# CoCoFlash_v1_04c.net
KiCad netlist of a schematic drawn in EAGLE
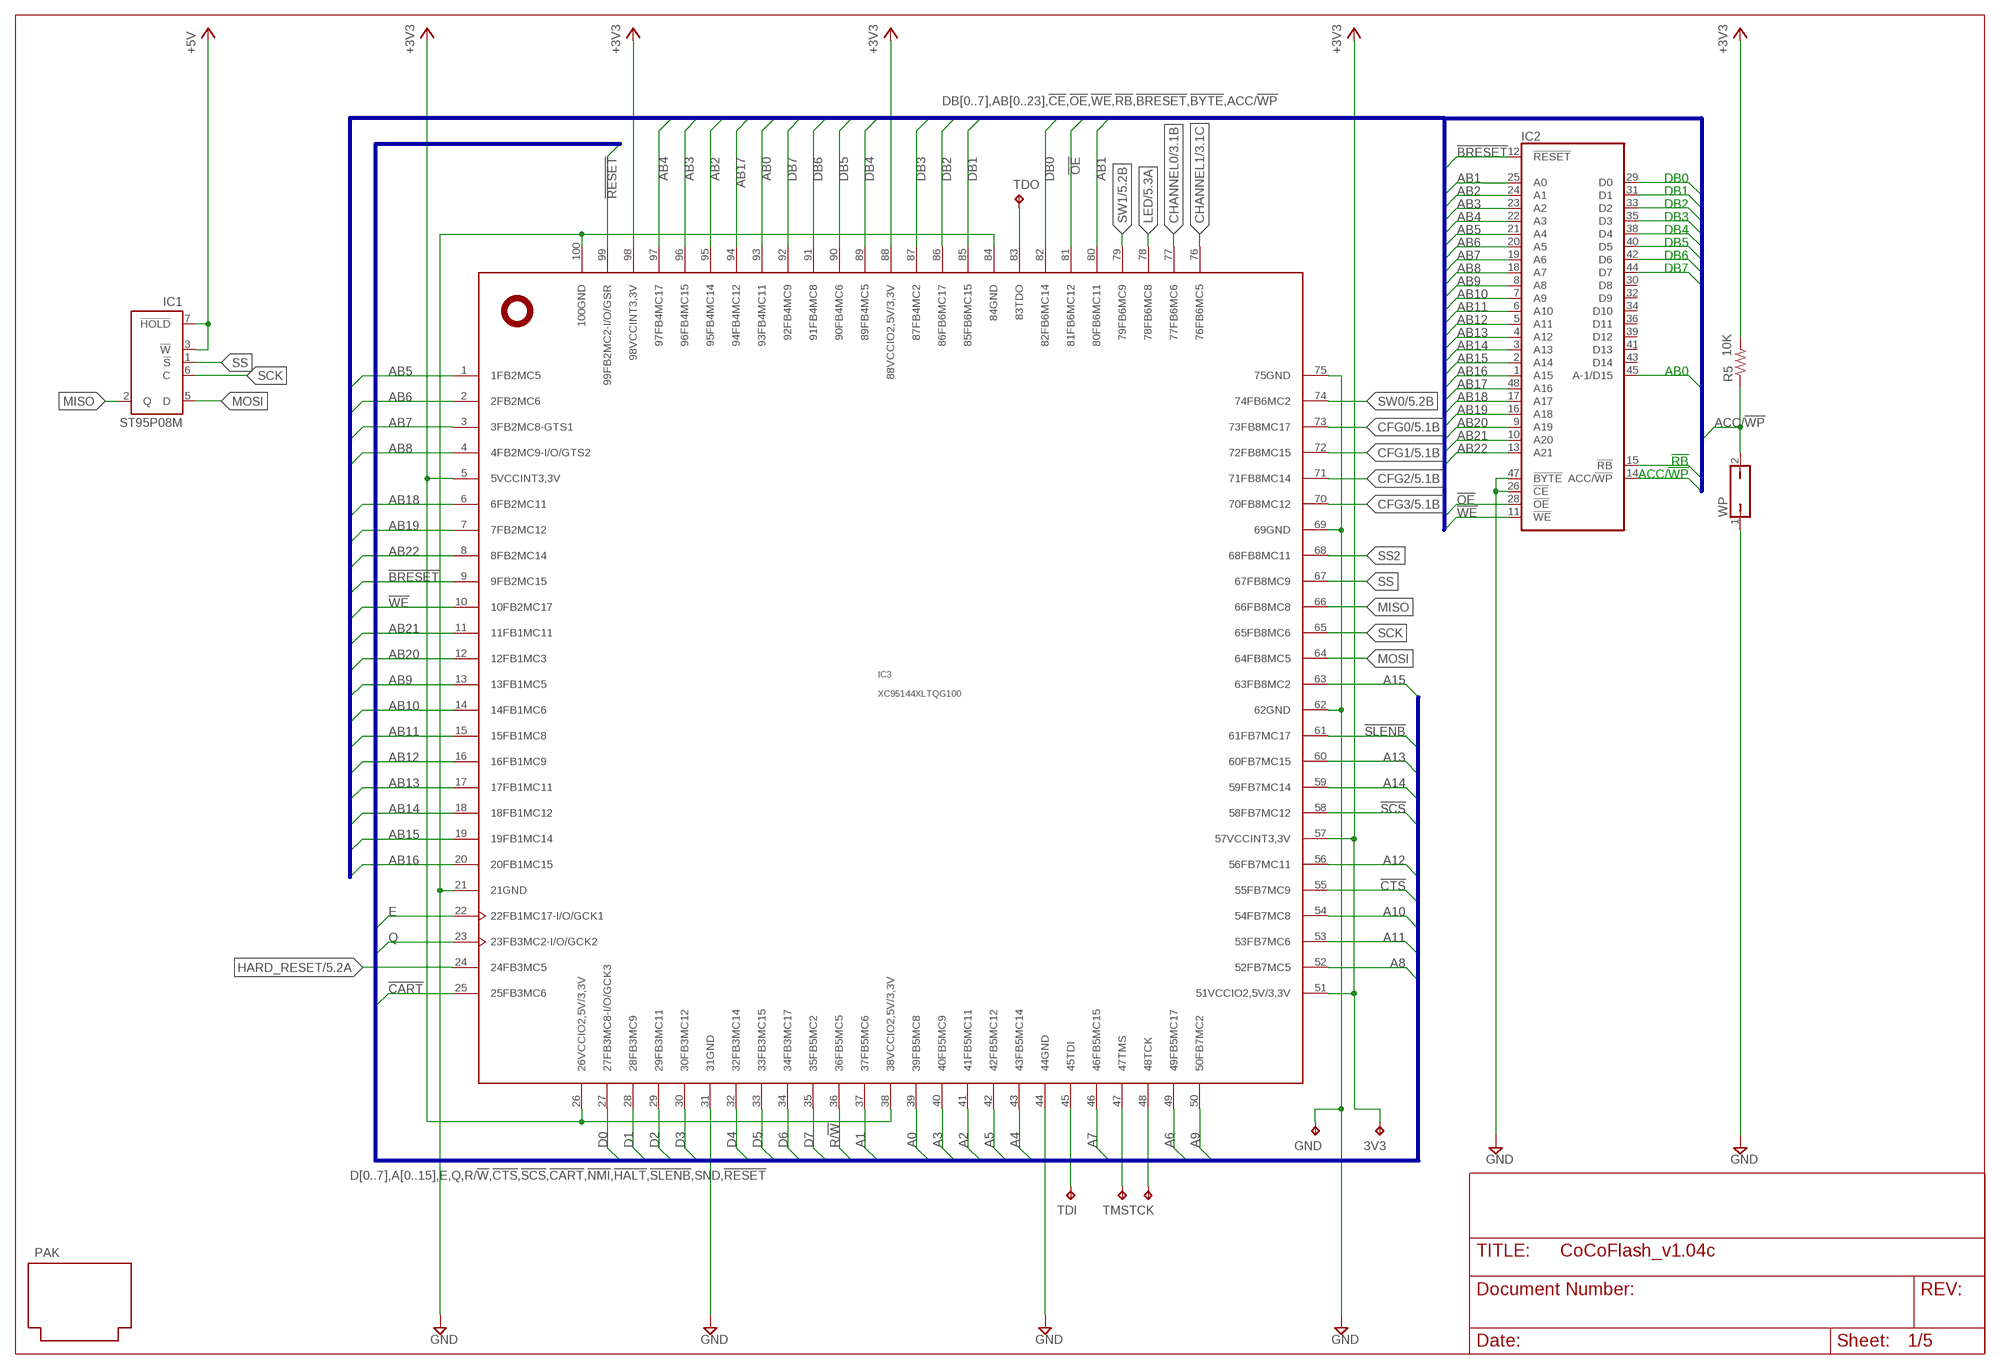
[diagram p0: schematic, sheet 1]
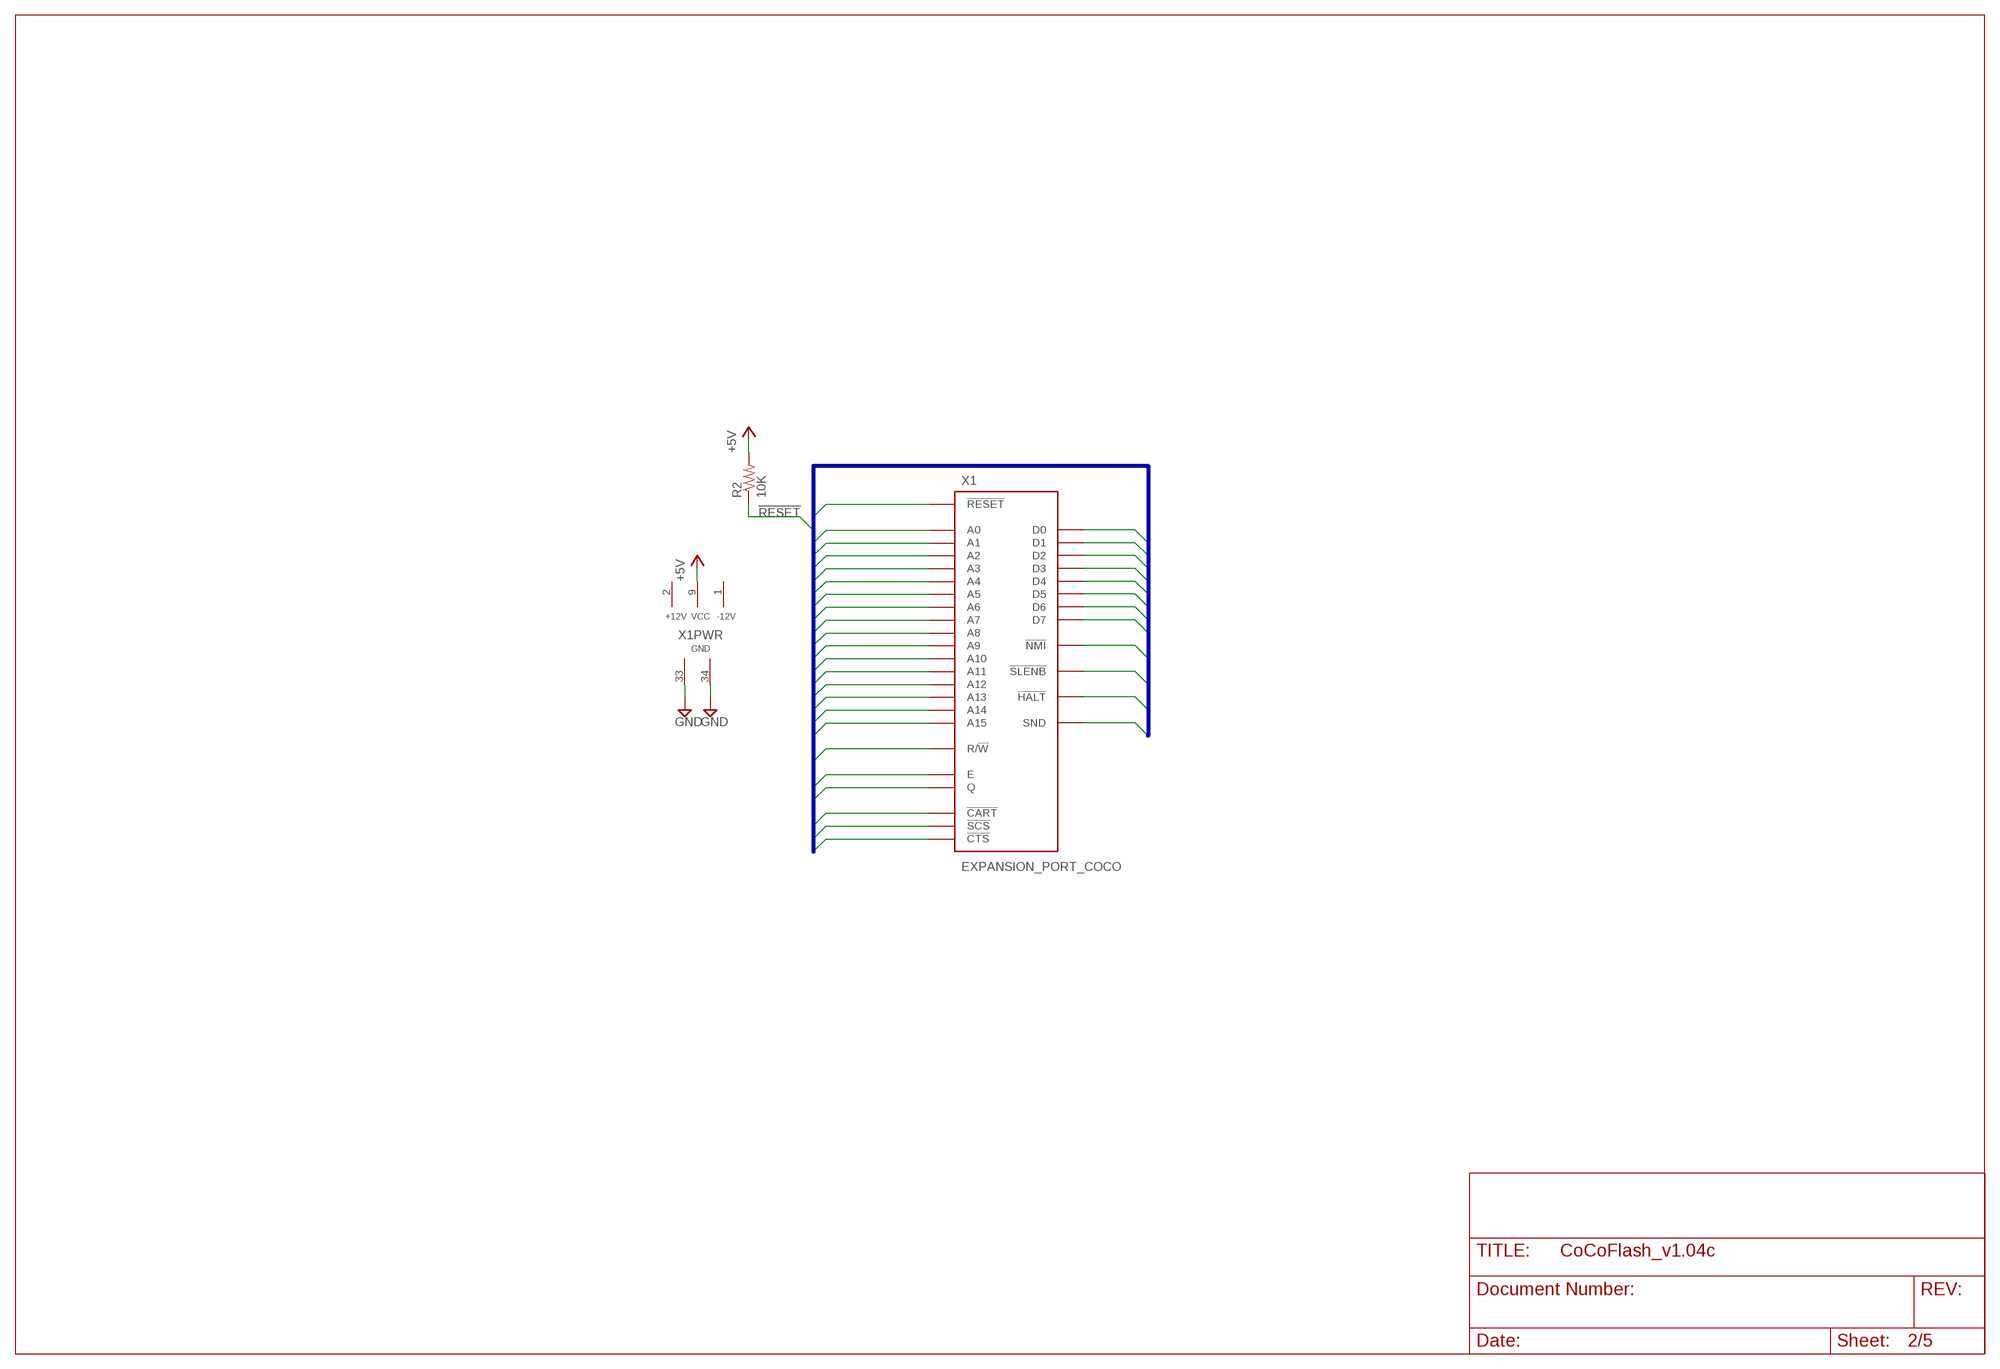
[diagram p1: schematic, sheet 2]
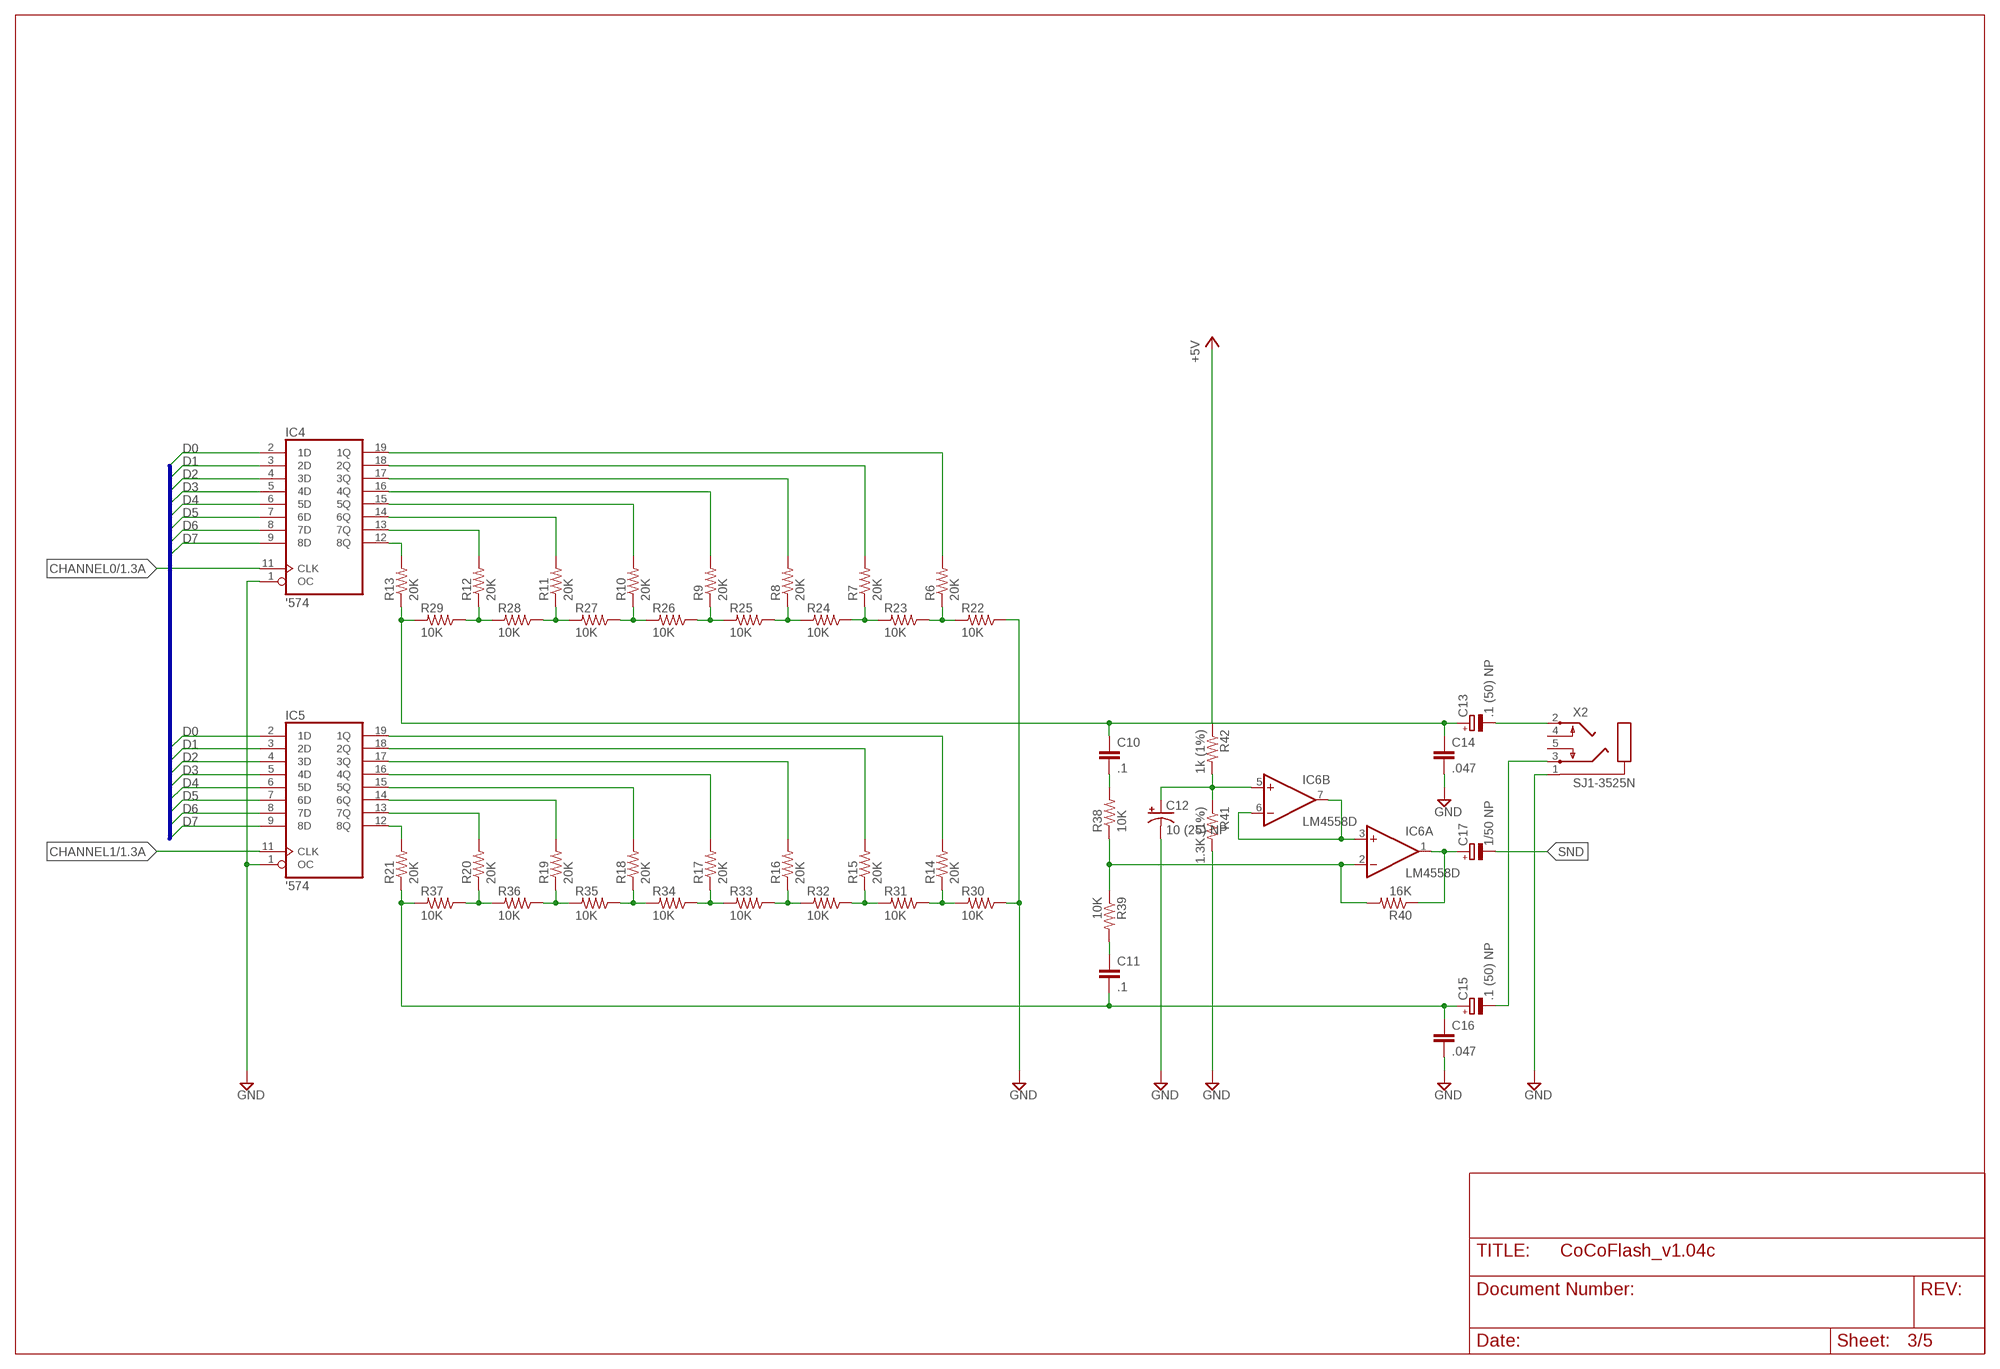
[diagram p2: schematic, sheet 3]
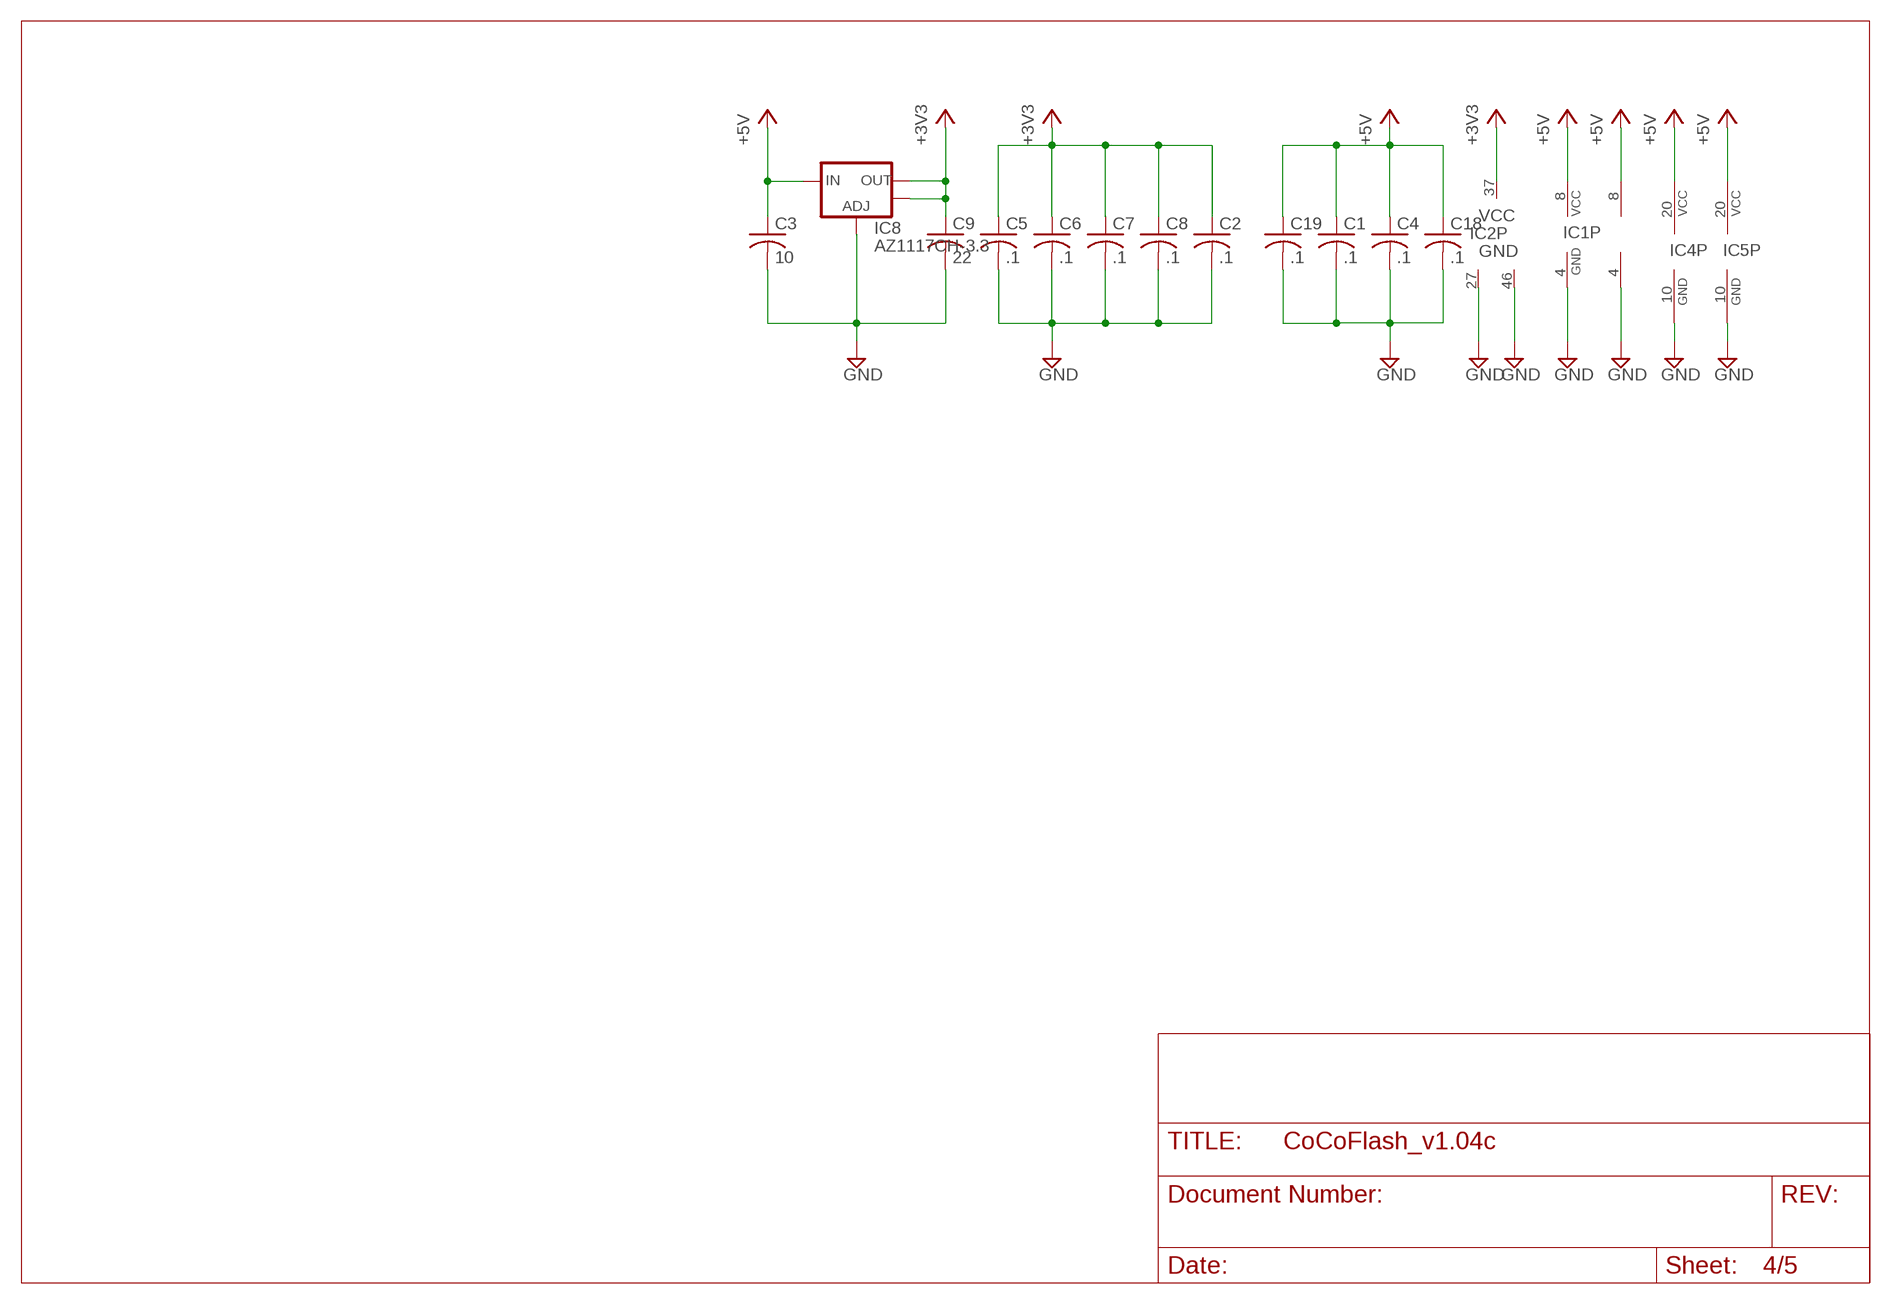
[diagram p3: schematic, sheet 4]
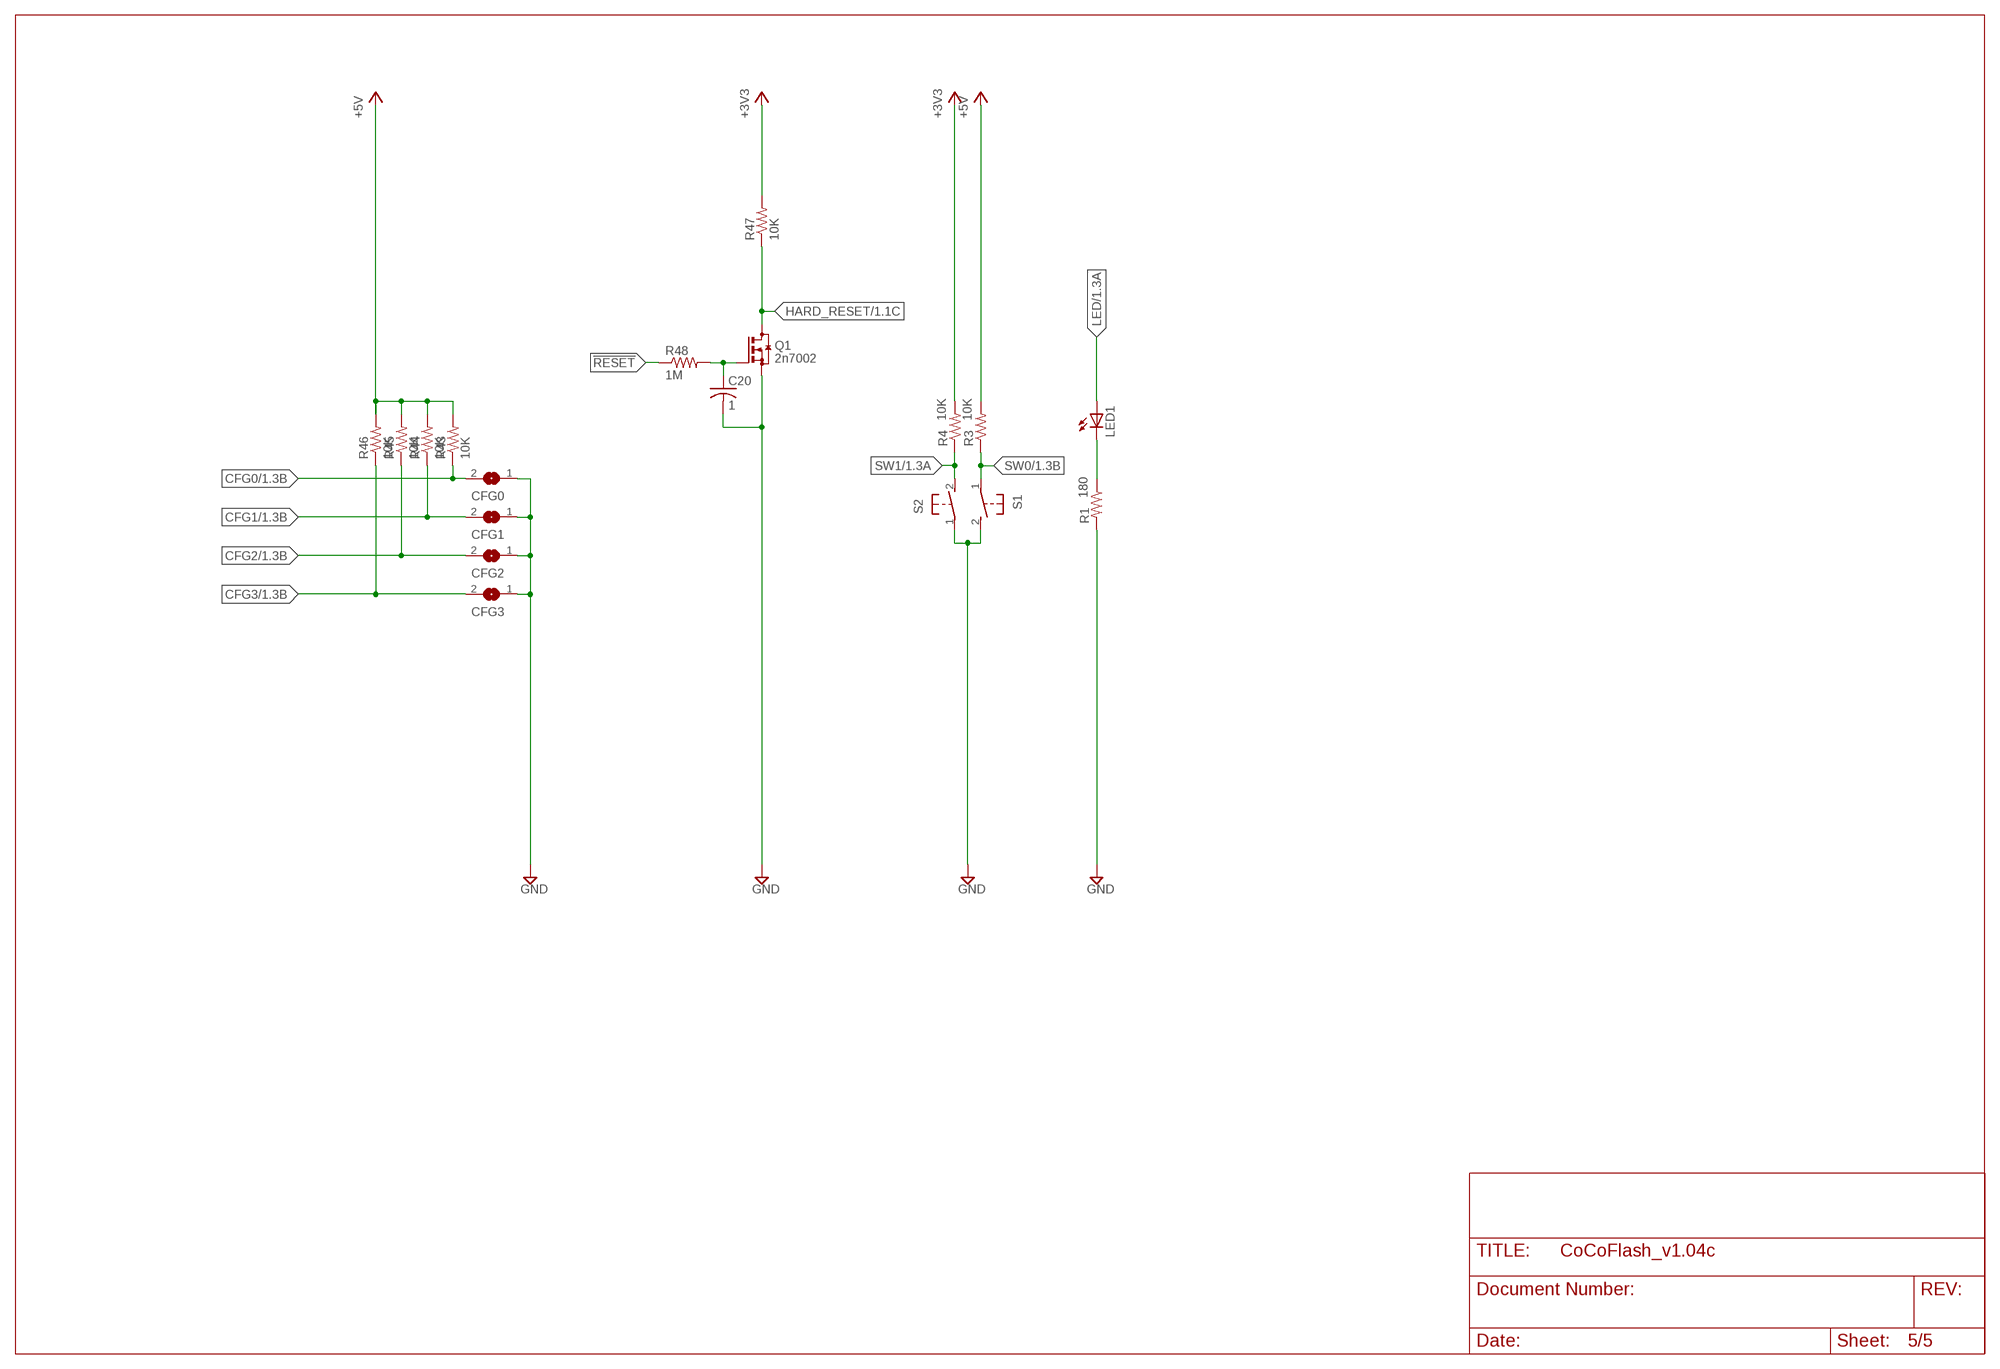
[diagram p4: schematic, sheet 5]

(export (version "E")
  (design (tool "Eeschema 10.0.6"))
  (components
    (comp (ref "R2")
      (value "10K")
      (footprint "eagle-import:R0402")
      (libsource (lib "eagle-import") (part "resistor_R-US_R0402"))
    )
    (comp (ref "X1")
      (value "EXPANSION_PORT_COCO")
      (footprint "eagle-import:MA20-2")
      (libsource (lib "eagle-import") (part "EXPANSION_PORT_COCO"))
    )
    (comp (ref "3V3")
      (value "TPTP08R")
      (footprint "eagle-import:TP08R")
      (libsource (lib "eagle-import") (part "TPTP08R"))
    )
    (comp (ref "GND")
      (value "TPTP08R")
      (footprint "eagle-import:TP08R")
      (libsource (lib "eagle-import") (part "TPTP08R"))
    )
    (comp (ref "IC1")
      (value "ST95P08M")
      (footprint "eagle-import:SO08")
      (libsource (lib "eagle-import") (part "ST95P08M"))
    )
    (comp (ref "IC2")
      (value "MX29LV640")
      (footprint "eagle-import:TSOP48")
      (libsource (lib "eagle-import") (part "MX29LV640"))
    )
    (comp (ref "IC3")
      (value "XC95144XLTQG100")
      (footprint "eagle-import:TQFP100")
      (libsource (lib "eagle-import") (part "XC95144XLTQG100"))
    )
    (comp (ref "PAK")
      (value "PROGRAM_PAK")
      (footprint "eagle-import:PROGRAM_PAK")
      (libsource (lib "eagle-import") (part "PROGRAM_PAK"))
    )
    (comp (ref "R5")
      (value "10K")
      (footprint "eagle-import:R0402")
      (libsource (lib "eagle-import") (part "R-US_R0402"))
    )
    (comp (ref "TCK")
      (value "TPTP08R")
      (footprint "eagle-import:TP08R")
      (libsource (lib "eagle-import") (part "TPTP08R"))
    )
    (comp (ref "TDI")
      (value "TPTP08R")
      (footprint "eagle-import:TP08R")
      (libsource (lib "eagle-import") (part "TPTP08R"))
    )
    (comp (ref "TDO")
      (value "TPTP08R")
      (footprint "eagle-import:TP08R")
      (libsource (lib "eagle-import") (part "TPTP08R"))
    )
    (comp (ref "TMS")
      (value "TPTP08R")
      (footprint "eagle-import:TP08R")
      (libsource (lib "eagle-import") (part "TPTP08R"))
    )
    (comp (ref "WP")
      (value "JP1Q")
      (footprint "eagle-import:JP1")
      (libsource (lib "eagle-import") (part "JP1Q"))
    )
    (comp (ref "C20")
      (value "1")
      (footprint "eagle-import:C0402")
      (libsource (lib "eagle-import") (part "C-USC0402"))
    )
    (comp (ref "CFG0")
      (value "SJ")
      (footprint "eagle-import:SJ")
      (libsource (lib "eagle-import") (part "SJ"))
    )
    (comp (ref "CFG1")
      (value "SJ")
      (footprint "eagle-import:SJ")
      (libsource (lib "eagle-import") (part "SJ"))
    )
    (comp (ref "CFG2")
      (value "SJ")
      (footprint "eagle-import:SJ")
      (libsource (lib "eagle-import") (part "SJ"))
    )
    (comp (ref "CFG3")
      (value "SJ")
      (footprint "eagle-import:SJ")
      (libsource (lib "eagle-import") (part "SJ"))
    )
    (comp (ref "LED1")
      (value "LED3MM")
      (footprint "eagle-import:LED3MM")
      (libsource (lib "eagle-import") (part "LED3MM"))
    )
    (comp (ref "Q1")
      (value "2n7002")
      (footprint "eagle-import:SOT23")
      (libsource (lib "eagle-import") (part "BSS123"))
    )
    (comp (ref "R1")
      (value "180")
      (footprint "eagle-import:R0402")
      (libsource (lib "eagle-import") (part "R-US_R0402"))
    )
    (comp (ref "R3")
      (value "10K")
      (footprint "eagle-import:R0402")
      (libsource (lib "eagle-import") (part "R-US_R0402"))
    )
    (comp (ref "R4")
      (value "10K")
      (footprint "eagle-import:R0402")
      (libsource (lib "eagle-import") (part "R-US_R0402"))
    )
    (comp (ref "R43")
      (value "10K")
      (footprint "eagle-import:R0402")
      (libsource (lib "eagle-import") (part "R-US_R0402"))
    )
    (comp (ref "R44")
      (value "10K")
      (footprint "eagle-import:R0402")
      (libsource (lib "eagle-import") (part "R-US_R0402"))
    )
    (comp (ref "R45")
      (value "10K")
      (footprint "eagle-import:R0402")
      (libsource (lib "eagle-import") (part "R-US_R0402"))
    )
    (comp (ref "R46")
      (value "10K")
      (footprint "eagle-import:R0402")
      (libsource (lib "eagle-import") (part "R-US_R0402"))
    )
    (comp (ref "R47")
      (value "10K")
      (footprint "eagle-import:R0402")
      (libsource (lib "eagle-import") (part "R-US_R0402"))
    )
    (comp (ref "R48")
      (value "1M")
      (footprint "eagle-import:R0402")
      (libsource (lib "eagle-import") (part "R-US_R0402"))
    )
    (comp (ref "S1")
      (value "31-XX")
      (footprint "eagle-import:B3F-31XX")
      (fields (field (name "MPN") "B3F-3100"))
      (libsource (lib "eagle-import") (part "31-XX"))
    )
    (comp (ref "S2")
      (value "31-XX")
      (footprint "eagle-import:B3F-31XX")
      (fields (field (name "MPN") "B3F-3100"))
      (libsource (lib "eagle-import") (part "31-XX"))
    )
    (comp (ref "C10")
      (value ".1")
      (footprint "eagle-import:C050-025X075")
      (libsource (lib "eagle-import") (part "C-EU050-025X075"))
    )
    (comp (ref "C11")
      (value ".1")
      (footprint "eagle-import:C050-025X075")
      (libsource (lib "eagle-import") (part "C-EU050-025X075"))
    )
    (comp (ref "C12")
      (value "10 (25) NP")
      (footprint "eagle-import:E1,8-4")
      (libsource (lib "eagle-import") (part "CPOL-USE1.8-4"))
    )
    (comp (ref "C13")
      (value ".1 (50) NP")
      (footprint "eagle-import:E1,8-4")
      (libsource (lib "eagle-import") (part "CPOL-EUE1.8-4"))
    )
    (comp (ref "C14")
      (value ".047")
      (footprint "eagle-import:C050-025X075")
      (libsource (lib "eagle-import") (part "C-EU050-025X075"))
    )
    (comp (ref "C15")
      (value ".1 (50) NP")
      (footprint "eagle-import:E1,8-4")
      (libsource (lib "eagle-import") (part "CPOL-EUE1.8-4"))
    )
    (comp (ref "C16")
      (value ".047")
      (footprint "eagle-import:C050-025X075")
      (libsource (lib "eagle-import") (part "C-EU050-025X075"))
    )
    (comp (ref "C17")
      (value "1/50 NP")
      (footprint "eagle-import:E1,8-4")
      (libsource (lib "eagle-import") (part "CPOL-EUE1.8-4"))
    )
    (comp (ref "IC4")
      (value "'574")
      (footprint "eagle-import:TSSOP20")
      (libsource (lib "eagle-import") (part "74574TWRHCT"))
    )
    (comp (ref "IC5")
      (value "'574")
      (footprint "eagle-import:TSSOP20")
      (libsource (lib "eagle-import") (part "74574TWRHCT"))
    )
    (comp (ref "IC6")
      (value "LM4558D")
      (footprint "eagle-import:SO08")
      (libsource (lib "eagle-import") (part "4558DLM"))
    )
    (comp (ref "R6")
      (value "20K")
      (footprint "eagle-import:R1206")
      (libsource (lib "eagle-import") (part "R-US_R1206"))
    )
    (comp (ref "R7")
      (value "20K")
      (footprint "eagle-import:R1206")
      (libsource (lib "eagle-import") (part "R-US_R1206"))
    )
    (comp (ref "R8")
      (value "20K")
      (footprint "eagle-import:R1206")
      (libsource (lib "eagle-import") (part "R-US_R1206"))
    )
    (comp (ref "R9")
      (value "20K")
      (footprint "eagle-import:R1206")
      (libsource (lib "eagle-import") (part "R-US_R1206"))
    )
    (comp (ref "R10")
      (value "20K")
      (footprint "eagle-import:R1206")
      (libsource (lib "eagle-import") (part "R-US_R1206"))
    )
    (comp (ref "R11")
      (value "20K")
      (footprint "eagle-import:R1206")
      (libsource (lib "eagle-import") (part "R-US_R1206"))
    )
    (comp (ref "R12")
      (value "20K")
      (footprint "eagle-import:R1206")
      (libsource (lib "eagle-import") (part "R-US_R1206"))
    )
    (comp (ref "R13")
      (value "20K")
      (footprint "eagle-import:R1206")
      (libsource (lib "eagle-import") (part "R-US_R1206"))
    )
    (comp (ref "R14")
      (value "20K")
      (footprint "eagle-import:R1206")
      (libsource (lib "eagle-import") (part "R-US_R1206"))
    )
    (comp (ref "R15")
      (value "20K")
      (footprint "eagle-import:R1206")
      (libsource (lib "eagle-import") (part "R-US_R1206"))
    )
    (comp (ref "R16")
      (value "20K")
      (footprint "eagle-import:R1206")
      (libsource (lib "eagle-import") (part "R-US_R1206"))
    )
    (comp (ref "R17")
      (value "20K")
      (footprint "eagle-import:R1206")
      (libsource (lib "eagle-import") (part "R-US_R1206"))
    )
    (comp (ref "R18")
      (value "20K")
      (footprint "eagle-import:R1206")
      (libsource (lib "eagle-import") (part "R-US_R1206"))
    )
    (comp (ref "R19")
      (value "20K")
      (footprint "eagle-import:R1206")
      (libsource (lib "eagle-import") (part "R-US_R1206"))
    )
    (comp (ref "R20")
      (value "20K")
      (footprint "eagle-import:R1206")
      (libsource (lib "eagle-import") (part "R-US_R1206"))
    )
    (comp (ref "R21")
      (value "20K")
      (footprint "eagle-import:R1206")
      (libsource (lib "eagle-import") (part "R-US_R1206"))
    )
    (comp (ref "R22")
      (value "10K")
      (footprint "eagle-import:R1206")
      (libsource (lib "eagle-import") (part "R-US_R1206"))
    )
    (comp (ref "R23")
      (value "10K")
      (footprint "eagle-import:R1206")
      (libsource (lib "eagle-import") (part "R-US_R1206"))
    )
    (comp (ref "R24")
      (value "10K")
      (footprint "eagle-import:R1206")
      (libsource (lib "eagle-import") (part "R-US_R1206"))
    )
    (comp (ref "R25")
      (value "10K")
      (footprint "eagle-import:R1206")
      (libsource (lib "eagle-import") (part "R-US_R1206"))
    )
    (comp (ref "R26")
      (value "10K")
      (footprint "eagle-import:R1206")
      (libsource (lib "eagle-import") (part "R-US_R1206"))
    )
    (comp (ref "R27")
      (value "10K")
      (footprint "eagle-import:R1206")
      (libsource (lib "eagle-import") (part "R-US_R1206"))
    )
    (comp (ref "R28")
      (value "10K")
      (footprint "eagle-import:R1206")
      (libsource (lib "eagle-import") (part "R-US_R1206"))
    )
    (comp (ref "R29")
      (value "10K")
      (footprint "eagle-import:R1206")
      (libsource (lib "eagle-import") (part "R-US_R1206"))
    )
    (comp (ref "R30")
      (value "10K")
      (footprint "eagle-import:R1206")
      (libsource (lib "eagle-import") (part "R-US_R1206"))
    )
    (comp (ref "R31")
      (value "10K")
      (footprint "eagle-import:R1206")
      (libsource (lib "eagle-import") (part "R-US_R1206"))
    )
    (comp (ref "R32")
      (value "10K")
      (footprint "eagle-import:R1206")
      (libsource (lib "eagle-import") (part "R-US_R1206"))
    )
    (comp (ref "R33")
      (value "10K")
      (footprint "eagle-import:R1206")
      (libsource (lib "eagle-import") (part "R-US_R1206"))
    )
    (comp (ref "R34")
      (value "10K")
      (footprint "eagle-import:R1206")
      (libsource (lib "eagle-import") (part "R-US_R1206"))
    )
    (comp (ref "R35")
      (value "10K")
      (footprint "eagle-import:R1206")
      (libsource (lib "eagle-import") (part "R-US_R1206"))
    )
    (comp (ref "R36")
      (value "10K")
      (footprint "eagle-import:R1206")
      (libsource (lib "eagle-import") (part "R-US_R1206"))
    )
    (comp (ref "R37")
      (value "10K")
      (footprint "eagle-import:R1206")
      (libsource (lib "eagle-import") (part "R-US_R1206"))
    )
    (comp (ref "R38")
      (value "10K")
      (footprint "eagle-import:R1206")
      (libsource (lib "eagle-import") (part "R-US_R1206"))
    )
    (comp (ref "R39")
      (value "10K")
      (footprint "eagle-import:R1206")
      (libsource (lib "eagle-import") (part "R-US_R1206"))
    )
    (comp (ref "R40")
      (value "16K")
      (footprint "eagle-import:R1206")
      (libsource (lib "eagle-import") (part "R-US_R1206"))
    )
    (comp (ref "R41")
      (value "1.3K (1%)")
      (footprint "eagle-import:R0402")
      (libsource (lib "eagle-import") (part "R-US_R0402"))
    )
    (comp (ref "R42")
      (value "1k (1%)")
      (footprint "eagle-import:R0402")
      (libsource (lib "eagle-import") (part "R-US_R0402"))
    )
    (comp (ref "X2")
      (value "SJ1-3525N")
      (footprint "eagle-import:SJ1-3525N")
      (libsource (lib "eagle-import") (part "SJ1-3525N"))
    )
    (comp (ref "C1")
      (value ".1")
      (footprint "eagle-import:C0402")
      (libsource (lib "eagle-import") (part "C-USC0402"))
    )
    (comp (ref "C2")
      (value ".1")
      (footprint "eagle-import:C0402")
      (libsource (lib "eagle-import") (part "C-USC0402"))
    )
    (comp (ref "C3")
      (value "10")
      (footprint "eagle-import:C0805")
      (libsource (lib "eagle-import") (part "C-USC0805"))
    )
    (comp (ref "C4")
      (value ".1")
      (footprint "eagle-import:C0402")
      (libsource (lib "eagle-import") (part "C-USC0402"))
    )
    (comp (ref "C5")
      (value ".1")
      (footprint "eagle-import:C0402")
      (libsource (lib "eagle-import") (part "C-USC0402"))
    )
    (comp (ref "C6")
      (value ".1")
      (footprint "eagle-import:C0402")
      (libsource (lib "eagle-import") (part "C-USC0402"))
    )
    (comp (ref "C7")
      (value ".1")
      (footprint "eagle-import:C0402")
      (libsource (lib "eagle-import") (part "C-USC0402"))
    )
    (comp (ref "C8")
      (value ".1")
      (footprint "eagle-import:C0402")
      (libsource (lib "eagle-import") (part "C-USC0402"))
    )
    (comp (ref "C9")
      (value "22")
      (footprint "eagle-import:C0805")
      (libsource (lib "eagle-import") (part "C-USC0805"))
    )
    (comp (ref "C18")
      (value ".1")
      (footprint "eagle-import:C0402")
      (libsource (lib "eagle-import") (part "C-USC0402"))
    )
    (comp (ref "C19")
      (value ".1")
      (footprint "eagle-import:C0402")
      (libsource (lib "eagle-import") (part "C-USC0402"))
    )
    (comp (ref "IC8")
      (value "AZ1117CH-3.3")
      (footprint "eagle-import:SOT223")
      (libsource (lib "eagle-import") (part "V_REG_LM1117SOT223"))
    )
  )
  (nets
    (net (code "6") (name "+3V3") (class "Default")
      (node (ref "3V3") (pin "TP") (pinfunction "TP_TP") (pintype "input"))
      (node (ref "C2") (pin "1") (pinfunction "1_1") (pintype "passive"))
      (node (ref "C5") (pin "1") (pinfunction "1_1") (pintype "passive"))
      (node (ref "C6") (pin "1") (pinfunction "1_1") (pintype "passive"))
      (node (ref "C7") (pin "1") (pinfunction "1_1") (pintype "passive"))
      (node (ref "C8") (pin "1") (pinfunction "1_1") (pintype "passive"))
      (node (ref "C9") (pin "1") (pinfunction "1_1") (pintype "passive"))
      (node (ref "IC2") (pin "37") (pinfunction "VCC_37") (pintype "power_in"))
      (node (ref "IC3") (pin "26") (pinfunction "26VCCIO2,5V/3,3V_26") (pintype "power_in"))
      (node (ref "IC3") (pin "38") (pinfunction "38VCCIO2,5V/3,3V_38") (pintype "power_in"))
      (node (ref "IC3") (pin "5") (pinfunction "5VCCINT3,3V_5") (pintype "power_in"))
      (node (ref "IC3") (pin "51") (pinfunction "51VCCIO2,5V/3,3V_51") (pintype "power_in"))
      (node (ref "IC3") (pin "57") (pinfunction "57VCCINT3,3V_57") (pintype "power_in"))
      (node (ref "IC3") (pin "88") (pinfunction "88VCCIO2,5V/3,3V_88") (pintype "power_in"))
      (node (ref "IC3") (pin "98") (pinfunction "98VCCINT3,3V_98") (pintype "bidirectional"))
      (node (ref "IC8") (pin "2") (pinfunction "OUT_2") (pintype "output"))
      (node (ref "IC8") (pin "4") (pinfunction "OUT_4") (pintype "output"))
      (node (ref "R4") (pin "2") (pinfunction "2_2") (pintype "passive"))
      (node (ref "R47") (pin "2") (pinfunction "2_2") (pintype "passive"))
      (node (ref "R5") (pin "2") (pinfunction "2_2") (pintype "passive"))
    )
    (net (code "7") (name "+5V") (class "Default")
      (node (ref "C1") (pin "1") (pinfunction "1_1") (pintype "passive"))
      (node (ref "C18") (pin "1") (pinfunction "1_1") (pintype "passive"))
      (node (ref "C19") (pin "1") (pinfunction "1_1") (pintype "passive"))
      (node (ref "C3") (pin "1") (pinfunction "1_1") (pintype "passive"))
      (node (ref "C4") (pin "1") (pinfunction "1_1") (pintype "passive"))
      (node (ref "IC1") (pin "3") (pinfunction "~{W}_3") (pintype "input"))
      (node (ref "IC1") (pin "7") (pinfunction "~{HOLD}_7") (pintype "input"))
      (node (ref "IC1") (pin "8") (pinfunction "VCC_8") (pintype "power_in"))
      (node (ref "IC4") (pin "20") (pinfunction "VCC_20") (pintype "power_in"))
      (node (ref "IC5") (pin "20") (pinfunction "VCC_20") (pintype "power_in"))
      (node (ref "IC6") (pin "8") (pinfunction "V+_8") (pintype "power_in"))
      (node (ref "IC8") (pin "3") (pinfunction "IN_3") (pintype "input"))
      (node (ref "R2") (pin "2") (pinfunction "2_2") (pintype "passive"))
      (node (ref "R3") (pin "2") (pinfunction "2_2") (pintype "passive"))
      (node (ref "R42") (pin "1") (pinfunction "1_1") (pintype "passive"))
      (node (ref "R43") (pin "2") (pinfunction "2_2") (pintype "passive"))
      (node (ref "R44") (pin "2") (pinfunction "2_2") (pintype "passive"))
      (node (ref "R45") (pin "2") (pinfunction "2_2") (pintype "passive"))
      (node (ref "R46") (pin "2") (pinfunction "2_2") (pintype "passive"))
      (node (ref "X1") (pin "9") (pinfunction "VCC_9") (pintype "power_in"))
    )
    (net (code "8") (name "+12V") (class "Default")
      (node (ref "X1") (pin "2") (pinfunction "+12V_2") (pintype "power_in"))
    )
    (net (code "9") (name "-12V") (class "Default")
      (node (ref "X1") (pin "1") (pinfunction "-12V_1") (pintype "power_in"))
    )
    (net (code "12") (name "A0") (class "Default")
      (node (ref "IC3") (pin "39") (pinfunction "39FB5MC8_39") (pintype "bidirectional"))
      (node (ref "X1") (pin "19") (pinfunction "A0_19") (pintype "passive"))
    )
    (net (code "13") (name "A1") (class "Default")
      (node (ref "IC3") (pin "37") (pinfunction "37FB5MC6_37") (pintype "bidirectional"))
      (node (ref "X1") (pin "20") (pinfunction "A1_20") (pintype "passive"))
    )
    (net (code "14") (name "A2") (class "Default")
      (node (ref "IC3") (pin "41") (pinfunction "41FB5MC11_41") (pintype "bidirectional"))
      (node (ref "X1") (pin "21") (pinfunction "A2_21") (pintype "passive"))
    )
    (net (code "15") (name "A3") (class "Default")
      (node (ref "IC3") (pin "40") (pinfunction "40FB5MC9_40") (pintype "bidirectional"))
      (node (ref "X1") (pin "22") (pinfunction "A3_22") (pintype "passive"))
    )
    (net (code "16") (name "A4") (class "Default")
      (node (ref "IC3") (pin "43") (pinfunction "43FB5MC14_43") (pintype "bidirectional"))
      (node (ref "X1") (pin "23") (pinfunction "A4_23") (pintype "passive"))
    )
    (net (code "17") (name "A5") (class "Default")
      (node (ref "IC3") (pin "42") (pinfunction "42FB5MC12_42") (pintype "bidirectional"))
      (node (ref "X1") (pin "24") (pinfunction "A5_24") (pintype "passive"))
    )
    (net (code "18") (name "A6") (class "Default")
      (node (ref "IC3") (pin "49") (pinfunction "49FB5MC17_49") (pintype "bidirectional"))
      (node (ref "X1") (pin "25") (pinfunction "A6_25") (pintype "passive"))
    )
    (net (code "19") (name "A7") (class "Default")
      (node (ref "IC3") (pin "46") (pinfunction "46FB5MC15_46") (pintype "bidirectional"))
      (node (ref "X1") (pin "26") (pinfunction "A7_26") (pintype "passive"))
    )
    (net (code "20") (name "A8") (class "Default")
      (node (ref "IC3") (pin "52") (pinfunction "52FB7MC5_52") (pintype "bidirectional"))
      (node (ref "X1") (pin "27") (pinfunction "A8_27") (pintype "passive"))
    )
    (net (code "21") (name "A9") (class "Default")
      (node (ref "IC3") (pin "50") (pinfunction "50FB7MC2_50") (pintype "bidirectional"))
      (node (ref "X1") (pin "28") (pinfunction "A9_28") (pintype "passive"))
    )
    (net (code "22") (name "A10") (class "Default")
      (node (ref "IC3") (pin "54") (pinfunction "54FB7MC8_54") (pintype "bidirectional"))
      (node (ref "X1") (pin "29") (pinfunction "A10_29") (pintype "passive"))
    )
    (net (code "23") (name "A11") (class "Default")
      (node (ref "IC3") (pin "53") (pinfunction "53FB7MC6_53") (pintype "bidirectional"))
      (node (ref "X1") (pin "30") (pinfunction "A11_30") (pintype "passive"))
    )
    (net (code "24") (name "A12") (class "Default")
      (node (ref "IC3") (pin "56") (pinfunction "56FB7MC11_56") (pintype "bidirectional"))
      (node (ref "X1") (pin "31") (pinfunction "A12_31") (pintype "passive"))
    )
    (net (code "25") (name "A13") (class "Default")
      (node (ref "IC3") (pin "60") (pinfunction "60FB7MC15_60") (pintype "bidirectional"))
      (node (ref "X1") (pin "37") (pinfunction "A13_37") (pintype "passive"))
    )
    (net (code "26") (name "A14") (class "Default")
      (node (ref "IC3") (pin "59") (pinfunction "59FB7MC14_59") (pintype "bidirectional"))
      (node (ref "X1") (pin "38") (pinfunction "A14_38") (pintype "passive"))
    )
    (net (code "27") (name "A15") (class "Default")
      (node (ref "IC3") (pin "63") (pinfunction "63FB8MC2_63") (pintype "bidirectional"))
      (node (ref "X1") (pin "39") (pinfunction "A15_39") (pintype "passive"))
    )
    (net (code "28") (name "AB0") (class "Default")
      (node (ref "IC2") (pin "45") (pinfunction "A-1/D15_45") (pintype "tri_state"))
      (node (ref "IC3") (pin "93") (pinfunction "93FB4MC11_93") (pintype "bidirectional"))
    )
    (net (code "29") (name "AB1") (class "Default")
      (node (ref "IC2") (pin "25") (pinfunction "A0_25") (pintype "input"))
      (node (ref "IC3") (pin "80") (pinfunction "80FB6MC11_80") (pintype "bidirectional"))
    )
    (net (code "30") (name "AB2") (class "Default")
      (node (ref "IC2") (pin "24") (pinfunction "A1_24") (pintype "input"))
      (node (ref "IC3") (pin "95") (pinfunction "95FB4MC14_95") (pintype "bidirectional"))
    )
    (net (code "31") (name "AB3") (class "Default")
      (node (ref "IC2") (pin "23") (pinfunction "A2_23") (pintype "input"))
      (node (ref "IC3") (pin "96") (pinfunction "96FB4MC15_96") (pintype "bidirectional"))
    )
    (net (code "32") (name "AB4") (class "Default")
      (node (ref "IC2") (pin "22") (pinfunction "A3_22") (pintype "input"))
      (node (ref "IC3") (pin "97") (pinfunction "97FB4MC17_97") (pintype "bidirectional"))
    )
    (net (code "33") (name "AB5") (class "Default")
      (node (ref "IC2") (pin "21") (pinfunction "A4_21") (pintype "input"))
      (node (ref "IC3") (pin "1") (pinfunction "1FB2MC5_1") (pintype "bidirectional"))
    )
    (net (code "34") (name "AB6") (class "Default")
      (node (ref "IC2") (pin "20") (pinfunction "A5_20") (pintype "input"))
      (node (ref "IC3") (pin "2") (pinfunction "2FB2MC6_2") (pintype "bidirectional"))
    )
    (net (code "35") (name "AB7") (class "Default")
      (node (ref "IC2") (pin "19") (pinfunction "A6_19") (pintype "input"))
      (node (ref "IC3") (pin "3") (pinfunction "3FB2MC8-GTS1_3") (pintype "bidirectional"))
    )
    (net (code "36") (name "AB8") (class "Default")
      (node (ref "IC2") (pin "18") (pinfunction "A7_18") (pintype "input"))
      (node (ref "IC3") (pin "4") (pinfunction "4FB2MC9-I/O/GTS2_4") (pintype "bidirectional"))
    )
    (net (code "37") (name "AB9") (class "Default")
      (node (ref "IC2") (pin "8") (pinfunction "A8_8") (pintype "input"))
      (node (ref "IC3") (pin "13") (pinfunction "13FB1MC5_13") (pintype "bidirectional"))
    )
    (net (code "38") (name "AB10") (class "Default")
      (node (ref "IC2") (pin "7") (pinfunction "A9_7") (pintype "input"))
      (node (ref "IC3") (pin "14") (pinfunction "14FB1MC6_14") (pintype "bidirectional"))
    )
    (net (code "39") (name "AB11") (class "Default")
      (node (ref "IC2") (pin "6") (pinfunction "A10_6") (pintype "input"))
      (node (ref "IC3") (pin "15") (pinfunction "15FB1MC8_15") (pintype "bidirectional"))
    )
    (net (code "40") (name "AB12") (class "Default")
      (node (ref "IC2") (pin "5") (pinfunction "A11_5") (pintype "input"))
      (node (ref "IC3") (pin "16") (pinfunction "16FB1MC9_16") (pintype "bidirectional"))
    )
    (net (code "41") (name "AB13") (class "Default")
      (node (ref "IC2") (pin "4") (pinfunction "A12_4") (pintype "input"))
      (node (ref "IC3") (pin "17") (pinfunction "17FB1MC11_17") (pintype "bidirectional"))
    )
    (net (code "42") (name "AB14") (class "Default")
      (node (ref "IC2") (pin "3") (pinfunction "A13_3") (pintype "input"))
      (node (ref "IC3") (pin "18") (pinfunction "18FB1MC12_18") (pintype "bidirectional"))
    )
    (net (code "43") (name "AB15") (class "Default")
      (node (ref "IC2") (pin "2") (pinfunction "A14_2") (pintype "input"))
      (node (ref "IC3") (pin "19") (pinfunction "19FB1MC14_19") (pintype "bidirectional"))
    )
    (net (code "44") (name "AB16") (class "Default")
      (node (ref "IC2") (pin "1") (pinfunction "A15_1") (pintype "input"))
      (node (ref "IC3") (pin "20") (pinfunction "20FB1MC15_20") (pintype "bidirectional"))
    )
    (net (code "45") (name "AB17") (class "Default")
      (node (ref "IC2") (pin "48") (pinfunction "A16_48") (pintype "input"))
      (node (ref "IC3") (pin "94") (pinfunction "94FB4MC12_94") (pintype "bidirectional"))
    )
    (net (code "46") (name "AB18") (class "Default")
      (node (ref "IC2") (pin "17") (pinfunction "A17_17") (pintype "input"))
      (node (ref "IC3") (pin "6") (pinfunction "6FB2MC11_6") (pintype "bidirectional"))
    )
    (net (code "47") (name "AB19") (class "Default")
      (node (ref "IC2") (pin "16") (pinfunction "A18_16") (pintype "input"))
      (node (ref "IC3") (pin "7") (pinfunction "7FB2MC12_7") (pintype "bidirectional"))
    )
    (net (code "48") (name "AB20") (class "Default")
      (node (ref "IC2") (pin "9") (pinfunction "A19_9") (pintype "input"))
      (node (ref "IC3") (pin "12") (pinfunction "12FB1MC3_12") (pintype "bidirectional"))
    )
    (net (code "49") (name "AB21") (class "Default")
      (node (ref "IC2") (pin "10") (pinfunction "A20_10") (pintype "input"))
      (node (ref "IC3") (pin "11") (pinfunction "11FB1MC11_11") (pintype "bidirectional"))
    )
    (net (code "50") (name "AB22") (class "Default")
      (node (ref "IC2") (pin "13") (pinfunction "A21_13") (pintype "input"))
      (node (ref "IC3") (pin "8") (pinfunction "8FB2MC14_8") (pintype "bidirectional"))
    )
    (net (code "51") (name "ACC{slash}~{WP}") (class "Default")
      (node (ref "IC2") (pin "14") (pinfunction "ACC/~{WP}_14") (pintype "output"))
      (node (ref "R5") (pin "1") (pinfunction "1_1") (pintype "passive"))
      (node (ref "WP") (pin "2") (pinfunction "2_2") (pintype "passive"))
    )
    (net (code "52") (name "CFG0") (class "Default")
      (node (ref "CFG0") (pin "2") (pinfunction "2_2") (pintype "passive"))
      (node (ref "IC3") (pin "73") (pinfunction "73FB8MC17_73") (pintype "bidirectional"))
      (node (ref "R43") (pin "1") (pinfunction "1_1") (pintype "passive"))
    )
    (net (code "53") (name "CFG1") (class "Default")
      (node (ref "CFG1") (pin "2") (pinfunction "2_2") (pintype "passive"))
      (node (ref "IC3") (pin "72") (pinfunction "72FB8MC15_72") (pintype "bidirectional"))
      (node (ref "R44") (pin "1") (pinfunction "1_1") (pintype "passive"))
    )
    (net (code "54") (name "CFG2") (class "Default")
      (node (ref "CFG2") (pin "2") (pinfunction "2_2") (pintype "passive"))
      (node (ref "IC3") (pin "71") (pinfunction "71FB8MC14_71") (pintype "bidirectional"))
      (node (ref "R45") (pin "1") (pinfunction "1_1") (pintype "passive"))
    )
    (net (code "55") (name "CFG3") (class "Default")
      (node (ref "CFG3") (pin "2") (pinfunction "2_2") (pintype "passive"))
      (node (ref "IC3") (pin "70") (pinfunction "70FB8MC12_70") (pintype "bidirectional"))
      (node (ref "R46") (pin "1") (pinfunction "1_1") (pintype "passive"))
    )
    (net (code "56") (name "CHANNEL0") (class "Default")
      (node (ref "IC3") (pin "77") (pinfunction "77FB6MC6_77") (pintype "bidirectional"))
      (node (ref "IC4") (pin "11") (pinfunction "CLK_11") (pintype "input"))
    )
    (net (code "57") (name "CHANNEL1") (class "Default")
      (node (ref "IC3") (pin "76") (pinfunction "76FB6MC5_76") (pintype "bidirectional"))
      (node (ref "IC5") (pin "11") (pinfunction "CLK_11") (pintype "input"))
    )
    (net (code "58") (name "D0") (class "Default")
      (node (ref "IC3") (pin "27") (pinfunction "27FB3MC8-I/O/GCK3_27") (pintype "bidirectional"))
      (node (ref "IC4") (pin "2") (pinfunction "1D_2") (pintype "input"))
      (node (ref "IC5") (pin "2") (pinfunction "1D_2") (pintype "input"))
      (node (ref "X1") (pin "10") (pinfunction "D0_10") (pintype "passive"))
    )
    (net (code "59") (name "D1") (class "Default")
      (node (ref "IC3") (pin "28") (pinfunction "28FB3MC9_28") (pintype "bidirectional"))
      (node (ref "IC4") (pin "3") (pinfunction "2D_3") (pintype "input"))
      (node (ref "IC5") (pin "3") (pinfunction "2D_3") (pintype "input"))
      (node (ref "X1") (pin "11") (pinfunction "D1_11") (pintype "passive"))
    )
    (net (code "60") (name "D2") (class "Default")
      (node (ref "IC3") (pin "29") (pinfunction "29FB3MC11_29") (pintype "bidirectional"))
      (node (ref "IC4") (pin "4") (pinfunction "3D_4") (pintype "input"))
      (node (ref "IC5") (pin "4") (pinfunction "3D_4") (pintype "input"))
      (node (ref "X1") (pin "12") (pinfunction "D2_12") (pintype "passive"))
    )
    (net (code "61") (name "D3") (class "Default")
      (node (ref "IC3") (pin "30") (pinfunction "30FB3MC12_30") (pintype "bidirectional"))
      (node (ref "IC4") (pin "5") (pinfunction "4D_5") (pintype "input"))
      (node (ref "IC5") (pin "5") (pinfunction "4D_5") (pintype "input"))
      (node (ref "X1") (pin "13") (pinfunction "D3_13") (pintype "passive"))
    )
    (net (code "62") (name "D4") (class "Default")
      (node (ref "IC3") (pin "32") (pinfunction "32FB3MC14_32") (pintype "bidirectional"))
      (node (ref "IC4") (pin "6") (pinfunction "5D_6") (pintype "input"))
      (node (ref "IC5") (pin "6") (pinfunction "5D_6") (pintype "input"))
      (node (ref "X1") (pin "14") (pinfunction "D4_14") (pintype "passive"))
    )
    (net (code "63") (name "D5") (class "Default")
      (node (ref "IC3") (pin "33") (pinfunction "33FB3MC15_33") (pintype "bidirectional"))
      (node (ref "IC4") (pin "7") (pinfunction "6D_7") (pintype "input"))
      (node (ref "IC5") (pin "7") (pinfunction "6D_7") (pintype "input"))
      (node (ref "X1") (pin "15") (pinfunction "D5_15") (pintype "passive"))
    )
    (net (code "64") (name "D6") (class "Default")
      (node (ref "IC3") (pin "34") (pinfunction "34FB3MC17_34") (pintype "bidirectional"))
      (node (ref "IC4") (pin "8") (pinfunction "7D_8") (pintype "input"))
      (node (ref "IC5") (pin "8") (pinfunction "7D_8") (pintype "input"))
      (node (ref "X1") (pin "16") (pinfunction "D6_16") (pintype "passive"))
    )
    (net (code "65") (name "D7") (class "Default")
      (node (ref "IC3") (pin "35") (pinfunction "35FB5MC2_35") (pintype "bidirectional"))
      (node (ref "IC4") (pin "9") (pinfunction "8D_9") (pintype "input"))
      (node (ref "IC5") (pin "9") (pinfunction "8D_9") (pintype "input"))
      (node (ref "X1") (pin "17") (pinfunction "D7_17") (pintype "passive"))
    )
    (net (code "66") (name "DB0") (class "Default")
      (node (ref "IC2") (pin "29") (pinfunction "D0_29") (pintype "tri_state"))
      (node (ref "IC3") (pin "82") (pinfunction "82FB6MC14_82") (pintype "bidirectional"))
    )
    (net (code "67") (name "DB1") (class "Default")
      (node (ref "IC2") (pin "31") (pinfunction "D1_31") (pintype "tri_state"))
      (node (ref "IC3") (pin "85") (pinfunction "85FB6MC15_85") (pintype "bidirectional"))
    )
    (net (code "68") (name "DB2") (class "Default")
      (node (ref "IC2") (pin "33") (pinfunction "D2_33") (pintype "tri_state"))
      (node (ref "IC3") (pin "86") (pinfunction "86FB6MC17_86") (pintype "bidirectional"))
    )
    (net (code "69") (name "DB3") (class "Default")
      (node (ref "IC2") (pin "35") (pinfunction "D3_35") (pintype "tri_state"))
      (node (ref "IC3") (pin "87") (pinfunction "87FB4MC2_87") (pintype "bidirectional"))
    )
    (net (code "70") (name "DB4") (class "Default")
      (node (ref "IC2") (pin "38") (pinfunction "D4_38") (pintype "tri_state"))
      (node (ref "IC3") (pin "89") (pinfunction "89FB4MC5_89") (pintype "bidirectional"))
    )
    (net (code "71") (name "DB5") (class "Default")
      (node (ref "IC2") (pin "40") (pinfunction "D5_40") (pintype "tri_state"))
      (node (ref "IC3") (pin "90") (pinfunction "90FB4MC6_90") (pintype "bidirectional"))
    )
    (net (code "72") (name "DB6") (class "Default")
      (node (ref "IC2") (pin "42") (pinfunction "D6_42") (pintype "tri_state"))
      (node (ref "IC3") (pin "91") (pinfunction "91FB4MC8_91") (pintype "bidirectional"))
    )
    (net (code "73") (name "DB7") (class "Default")
      (node (ref "IC2") (pin "44") (pinfunction "D7_44") (pintype "tri_state"))
      (node (ref "IC3") (pin "92") (pinfunction "92FB4MC9_92") (pintype "bidirectional"))
    )
    (net (code "74") (name "E") (class "Default")
      (node (ref "IC3") (pin "22") (pinfunction "22FB1MC17-I/O/GCK1_22") (pintype "bidirectional"))
      (node (ref "X1") (pin "6") (pinfunction "E_6") (pintype "passive"))
    )
    (net (code "75") (name "GND") (class "Default")
      (node (ref "C1") (pin "2") (pinfunction "2_2") (pintype "passive"))
      (node (ref "C12") (pin "-") (pinfunction "-_-") (pintype "passive"))
      (node (ref "C14") (pin "2") (pinfunction "2_2") (pintype "passive"))
      (node (ref "C16") (pin "2") (pinfunction "2_2") (pintype "passive"))
      (node (ref "C18") (pin "2") (pinfunction "2_2") (pintype "passive"))
      (node (ref "C19") (pin "2") (pinfunction "2_2") (pintype "passive"))
      (node (ref "C2") (pin "2") (pinfunction "2_2") (pintype "passive"))
      (node (ref "C20") (pin "2") (pinfunction "2_2") (pintype "passive"))
      (node (ref "C3") (pin "2") (pinfunction "2_2") (pintype "passive"))
      (node (ref "C4") (pin "2") (pinfunction "2_2") (pintype "passive"))
      (node (ref "C5") (pin "2") (pinfunction "2_2") (pintype "passive"))
      (node (ref "C6") (pin "2") (pinfunction "2_2") (pintype "passive"))
      (node (ref "C7") (pin "2") (pinfunction "2_2") (pintype "passive"))
      (node (ref "C8") (pin "2") (pinfunction "2_2") (pintype "passive"))
      (node (ref "C9") (pin "2") (pinfunction "2_2") (pintype "passive"))
      (node (ref "CFG0") (pin "1") (pinfunction "1_1") (pintype "passive"))
      (node (ref "CFG1") (pin "1") (pinfunction "1_1") (pintype "passive"))
      (node (ref "CFG2") (pin "1") (pinfunction "1_1") (pintype "passive"))
      (node (ref "CFG3") (pin "1") (pinfunction "1_1") (pintype "passive"))
      (node (ref "GND") (pin "TP") (pinfunction "TP_TP") (pintype "input"))
      (node (ref "IC1") (pin "4") (pinfunction "GND_4") (pintype "power_in"))
      (node (ref "IC2") (pin "26") (pinfunction "~{CE}_26") (pintype "input"))
      (node (ref "IC2") (pin "27") (pinfunction "GND_27") (pintype "power_in"))
      (node (ref "IC2") (pin "46") (pinfunction "GND_46") (pintype "power_in"))
      (node (ref "IC2") (pin "47") (pinfunction "~{BYTE}_47") (pintype "input"))
      (node (ref "IC3") (pin "100") (pinfunction "100GND_100") (pintype "power_in"))
      (node (ref "IC3") (pin "21") (pinfunction "21GND_21") (pintype "power_in"))
      (node (ref "IC3") (pin "31") (pinfunction "31GND_31") (pintype "power_in"))
      (node (ref "IC3") (pin "44") (pinfunction "44GND_44") (pintype "power_in"))
      (node (ref "IC3") (pin "62") (pinfunction "62GND_62") (pintype "power_in"))
      (node (ref "IC3") (pin "69") (pinfunction "69GND_69") (pintype "power_in"))
      (node (ref "IC3") (pin "75") (pinfunction "75GND_75") (pintype "power_in"))
      (node (ref "IC3") (pin "84") (pinfunction "84GND_84") (pintype "power_in"))
      (node (ref "IC4") (pin "1") (pinfunction "OC_1") (pintype "input"))
      (node (ref "IC4") (pin "10") (pinfunction "GND_10") (pintype "power_in"))
      (node (ref "IC5") (pin "1") (pinfunction "OC_1") (pintype "input"))
      (node (ref "IC5") (pin "10") (pinfunction "GND_10") (pintype "power_in"))
      (node (ref "IC6") (pin "4") (pinfunction "V-_4") (pintype "power_in"))
      (node (ref "IC8") (pin "1") (pinfunction "ADJ_1") (pintype "input"))
      (node (ref "Q1") (pin "2") (pinfunction "S_2") (pintype "passive"))
      (node (ref "R1") (pin "2") (pinfunction "2_2") (pintype "passive"))
      (node (ref "R22") (pin "1") (pinfunction "1_1") (pintype "passive"))
      (node (ref "R30") (pin "1") (pinfunction "1_1") (pintype "passive"))
      (node (ref "R41") (pin "2") (pinfunction "2_2") (pintype "passive"))
      (node (ref "S1") (pin "2") (pinfunction "S_2") (pintype "passive"))
      (node (ref "S2") (pin "1") (pinfunction "P_1") (pintype "passive"))
      (node (ref "WP") (pin "1") (pinfunction "1_1") (pintype "passive"))
      (node (ref "X1") (pin "33") (pinfunction "GND_33") (pintype "power_in"))
      (node (ref "X1") (pin "34") (pinfunction "GND_34") (pintype "power_in"))
      (node (ref "X2") (pin "1") (pinfunction "1_1") (pintype "passive"))
    )
    (net (code "76") (name "HARD_RESET") (class "Default")
      (node (ref "IC3") (pin "24") (pinfunction "24FB3MC5_24") (pintype "bidirectional"))
      (node (ref "Q1") (pin "3") (pinfunction "D_3") (pintype "passive"))
      (node (ref "R47") (pin "1") (pinfunction "1_1") (pintype "passive"))
    )
    (net (code "77") (name "LED") (class "Default")
      (node (ref "IC3") (pin "78") (pinfunction "78FB6MC8_78") (pintype "bidirectional"))
      (node (ref "LED1") (pin "A") (pinfunction "A_A") (pintype "passive"))
    )
    (net (code "78") (name "MISO") (class "Default")
      (node (ref "IC1") (pin "2") (pinfunction "Q_2") (pintype "tri_state"))
      (node (ref "IC3") (pin "66") (pinfunction "66FB8MC8_66") (pintype "bidirectional"))
    )
    (net (code "79") (name "MOSI") (class "Default")
      (node (ref "IC1") (pin "5") (pinfunction "D_5") (pintype "input"))
      (node (ref "IC3") (pin "64") (pinfunction "64FB8MC5_64") (pintype "bidirectional"))
    )
    (net (code "80") (name "Net-(C10-Pad1)") (class "Default")
      (node (ref "C10") (pin "1") (pinfunction "1_1") (pintype "passive"))
      (node (ref "C13") (pin "+") (pinfunction "+_+") (pintype "passive"))
      (node (ref "C14") (pin "1") (pinfunction "1_1") (pintype "passive"))
      (node (ref "R13") (pin "1") (pinfunction "1_1") (pintype "passive"))
      (node (ref "R29") (pin "2") (pinfunction "2_2") (pintype "passive"))
    )
    (net (code "81") (name "Net-(C10-Pad2)") (class "Default")
      (node (ref "C10") (pin "2") (pinfunction "2_2") (pintype "passive"))
      (node (ref "R38") (pin "2") (pinfunction "2_2") (pintype "passive"))
    )
    (net (code "82") (name "Net-(C11-Pad1)") (class "Default")
      (node (ref "C11") (pin "1") (pinfunction "1_1") (pintype "passive"))
      (node (ref "R39") (pin "2") (pinfunction "2_2") (pintype "passive"))
    )
    (net (code "83") (name "Net-(C11-Pad2)") (class "Default")
      (node (ref "C11") (pin "2") (pinfunction "2_2") (pintype "passive"))
      (node (ref "C15") (pin "+") (pinfunction "+_+") (pintype "passive"))
      (node (ref "C16") (pin "1") (pinfunction "1_1") (pintype "passive"))
      (node (ref "R21") (pin "1") (pinfunction "1_1") (pintype "passive"))
      (node (ref "R37") (pin "2") (pinfunction "2_2") (pintype "passive"))
    )
    (net (code "84") (name "Net-(C13-Pad-)") (class "Default")
      (node (ref "C13") (pin "-") (pinfunction "-_-") (pintype "passive"))
      (node (ref "X2") (pin "2") (pinfunction "2_2") (pintype "passive"))
    )
    (net (code "85") (name "Net-(C15-Pad-)") (class "Default")
      (node (ref "C15") (pin "-") (pinfunction "-_-") (pintype "passive"))
      (node (ref "X2") (pin "3") (pinfunction "3_3") (pintype "passive"))
    )
    (net (code "86") (name "Net-(IC3-45TDI)") (class "Default")
      (node (ref "IC3") (pin "45") (pinfunction "45TDI_45") (pintype "bidirectional"))
      (node (ref "TDI") (pin "TP") (pinfunction "TP_TP") (pintype "input"))
    )
    (net (code "87") (name "Net-(IC3-47TMS)") (class "Default")
      (node (ref "IC3") (pin "47") (pinfunction "47TMS_47") (pintype "bidirectional"))
      (node (ref "TMS") (pin "TP") (pinfunction "TP_TP") (pintype "input"))
    )
    (net (code "88") (name "Net-(IC3-48TCK)") (class "Default")
      (node (ref "IC3") (pin "48") (pinfunction "48TCK_48") (pintype "bidirectional"))
      (node (ref "TCK") (pin "TP") (pinfunction "TP_TP") (pintype "input"))
    )
    (net (code "89") (name "Net-(IC3-83TDO)") (class "Default")
      (node (ref "IC3") (pin "83") (pinfunction "83TDO_83") (pintype "bidirectional"))
      (node (ref "TDO") (pin "TP") (pinfunction "TP_TP") (pintype "input"))
    )
    (net (code "90") (name "Net-(IC4A-1Q)") (class "Default")
      (node (ref "IC4") (pin "19") (pinfunction "1Q_19") (pintype "tri_state"))
      (node (ref "R6") (pin "2") (pinfunction "2_2") (pintype "passive"))
    )
    (net (code "91") (name "Net-(IC4A-2Q)") (class "Default")
      (node (ref "IC4") (pin "18") (pinfunction "2Q_18") (pintype "tri_state"))
      (node (ref "R7") (pin "2") (pinfunction "2_2") (pintype "passive"))
    )
    (net (code "92") (name "Net-(IC4A-3Q)") (class "Default")
      (node (ref "IC4") (pin "17") (pinfunction "3Q_17") (pintype "tri_state"))
      (node (ref "R8") (pin "2") (pinfunction "2_2") (pintype "passive"))
    )
    (net (code "93") (name "Net-(IC4A-4Q)") (class "Default")
      (node (ref "IC4") (pin "16") (pinfunction "4Q_16") (pintype "tri_state"))
      (node (ref "R9") (pin "2") (pinfunction "2_2") (pintype "passive"))
    )
    (net (code "94") (name "Net-(IC4A-5Q)") (class "Default")
      (node (ref "IC4") (pin "15") (pinfunction "5Q_15") (pintype "tri_state"))
      (node (ref "R10") (pin "2") (pinfunction "2_2") (pintype "passive"))
    )
    (net (code "95") (name "Net-(IC4A-6Q)") (class "Default")
      (node (ref "IC4") (pin "14") (pinfunction "6Q_14") (pintype "tri_state"))
      (node (ref "R11") (pin "2") (pinfunction "2_2") (pintype "passive"))
    )
    (net (code "96") (name "Net-(IC4A-7Q)") (class "Default")
      (node (ref "IC4") (pin "13") (pinfunction "7Q_13") (pintype "tri_state"))
      (node (ref "R12") (pin "2") (pinfunction "2_2") (pintype "passive"))
    )
    (net (code "97") (name "Net-(IC4A-8Q)") (class "Default")
      (node (ref "IC4") (pin "12") (pinfunction "8Q_12") (pintype "tri_state"))
      (node (ref "R13") (pin "2") (pinfunction "2_2") (pintype "passive"))
    )
    (net (code "98") (name "Net-(IC5A-1Q)") (class "Default")
      (node (ref "IC5") (pin "19") (pinfunction "1Q_19") (pintype "tri_state"))
      (node (ref "R14") (pin "2") (pinfunction "2_2") (pintype "passive"))
    )
    (net (code "99") (name "Net-(IC5A-2Q)") (class "Default")
      (node (ref "IC5") (pin "18") (pinfunction "2Q_18") (pintype "tri_state"))
      (node (ref "R15") (pin "2") (pinfunction "2_2") (pintype "passive"))
    )
    (net (code "100") (name "Net-(IC5A-3Q)") (class "Default")
      (node (ref "IC5") (pin "17") (pinfunction "3Q_17") (pintype "tri_state"))
      (node (ref "R16") (pin "2") (pinfunction "2_2") (pintype "passive"))
    )
    (net (code "101") (name "Net-(IC5A-4Q)") (class "Default")
      (node (ref "IC5") (pin "16") (pinfunction "4Q_16") (pintype "tri_state"))
      (node (ref "R17") (pin "2") (pinfunction "2_2") (pintype "passive"))
    )
    (net (code "102") (name "Net-(IC5A-5Q)") (class "Default")
      (node (ref "IC5") (pin "15") (pinfunction "5Q_15") (pintype "tri_state"))
      (node (ref "R18") (pin "2") (pinfunction "2_2") (pintype "passive"))
    )
    (net (code "103") (name "Net-(IC5A-6Q)") (class "Default")
      (node (ref "IC5") (pin "14") (pinfunction "6Q_14") (pintype "tri_state"))
      (node (ref "R19") (pin "2") (pinfunction "2_2") (pintype "passive"))
    )
    (net (code "104") (name "Net-(IC5A-7Q)") (class "Default")
      (node (ref "IC5") (pin "13") (pinfunction "7Q_13") (pintype "tri_state"))
      (node (ref "R20") (pin "2") (pinfunction "2_2") (pintype "passive"))
    )
    (net (code "105") (name "Net-(IC5A-8Q)") (class "Default")
      (node (ref "IC5") (pin "12") (pinfunction "8Q_12") (pintype "tri_state"))
      (node (ref "R21") (pin "2") (pinfunction "2_2") (pintype "passive"))
    )
    (net (code "106") (name "Net-(IC6A-+IN)") (class "Default")
      (node (ref "IC6") (pin "3") (pinfunction "+IN_3") (pintype "input"))
      (node (ref "IC6") (pin "6") (pinfunction "-IN_6") (pintype "input"))
      (node (ref "IC6") (pin "7") (pinfunction "OUT_7") (pintype "output"))
    )
    (net (code "107") (name "Net-(IC6A--IN)") (class "Default")
      (node (ref "IC6") (pin "2") (pinfunction "-IN_2") (pintype "input"))
      (node (ref "R38") (pin "1") (pinfunction "1_1") (pintype "passive"))
      (node (ref "R39") (pin "1") (pinfunction "1_1") (pintype "passive"))
      (node (ref "R40") (pin "2") (pinfunction "2_2") (pintype "passive"))
    )
    (net (code "108") (name "Net-(IC6A-OUT)") (class "Default")
      (node (ref "C17") (pin "+") (pinfunction "+_+") (pintype "passive"))
      (node (ref "IC6") (pin "1") (pinfunction "OUT_1") (pintype "output"))
      (node (ref "R40") (pin "1") (pinfunction "1_1") (pintype "passive"))
    )
    (net (code "109") (name "Net-(IC6B-+IN)") (class "Default")
      (node (ref "C12") (pin "+") (pinfunction "+_+") (pintype "passive"))
      (node (ref "IC6") (pin "5") (pinfunction "+IN_5") (pintype "input"))
      (node (ref "R41") (pin "1") (pinfunction "1_1") (pintype "passive"))
      (node (ref "R42") (pin "2") (pinfunction "2_2") (pintype "passive"))
    )
    (net (code "110") (name "Net-(LED1-C)") (class "Default")
      (node (ref "LED1") (pin "K") (pinfunction "C_K") (pintype "passive"))
      (node (ref "R1") (pin "1") (pinfunction "1_1") (pintype "passive"))
    )
    (net (code "111") (name "Net-(Q1-G)") (class "Default")
      (node (ref "C20") (pin "1") (pinfunction "1_1") (pintype "passive"))
      (node (ref "Q1") (pin "1") (pinfunction "G_1") (pintype "passive"))
      (node (ref "R48") (pin "2") (pinfunction "2_2") (pintype "passive"))
    )
    (net (code "112") (name "Net-(R10-Pad1)") (class "Default")
      (node (ref "R10") (pin "1") (pinfunction "1_1") (pintype "passive"))
      (node (ref "R26") (pin "2") (pinfunction "2_2") (pintype "passive"))
      (node (ref "R27") (pin "1") (pinfunction "1_1") (pintype "passive"))
    )
    (net (code "113") (name "Net-(R11-Pad1)") (class "Default")
      (node (ref "R11") (pin "1") (pinfunction "1_1") (pintype "passive"))
      (node (ref "R27") (pin "2") (pinfunction "2_2") (pintype "passive"))
      (node (ref "R28") (pin "1") (pinfunction "1_1") (pintype "passive"))
    )
    (net (code "114") (name "Net-(R12-Pad1)") (class "Default")
      (node (ref "R12") (pin "1") (pinfunction "1_1") (pintype "passive"))
      (node (ref "R28") (pin "2") (pinfunction "2_2") (pintype "passive"))
      (node (ref "R29") (pin "1") (pinfunction "1_1") (pintype "passive"))
    )
    (net (code "115") (name "Net-(R14-Pad1)") (class "Default")
      (node (ref "R14") (pin "1") (pinfunction "1_1") (pintype "passive"))
      (node (ref "R30") (pin "2") (pinfunction "2_2") (pintype "passive"))
      (node (ref "R31") (pin "1") (pinfunction "1_1") (pintype "passive"))
    )
    (net (code "116") (name "Net-(R15-Pad1)") (class "Default")
      (node (ref "R15") (pin "1") (pinfunction "1_1") (pintype "passive"))
      (node (ref "R31") (pin "2") (pinfunction "2_2") (pintype "passive"))
      (node (ref "R32") (pin "1") (pinfunction "1_1") (pintype "passive"))
    )
    (net (code "117") (name "Net-(R16-Pad1)") (class "Default")
      (node (ref "R16") (pin "1") (pinfunction "1_1") (pintype "passive"))
      (node (ref "R32") (pin "2") (pinfunction "2_2") (pintype "passive"))
      (node (ref "R33") (pin "1") (pinfunction "1_1") (pintype "passive"))
    )
    (net (code "118") (name "Net-(R17-Pad1)") (class "Default")
      (node (ref "R17") (pin "1") (pinfunction "1_1") (pintype "passive"))
      (node (ref "R33") (pin "2") (pinfunction "2_2") (pintype "passive"))
      (node (ref "R34") (pin "1") (pinfunction "1_1") (pintype "passive"))
    )
    (net (code "119") (name "Net-(R18-Pad1)") (class "Default")
      (node (ref "R18") (pin "1") (pinfunction "1_1") (pintype "passive"))
      (node (ref "R34") (pin "2") (pinfunction "2_2") (pintype "passive"))
      (node (ref "R35") (pin "1") (pinfunction "1_1") (pintype "passive"))
    )
    (net (code "120") (name "Net-(R19-Pad1)") (class "Default")
      (node (ref "R19") (pin "1") (pinfunction "1_1") (pintype "passive"))
      (node (ref "R35") (pin "2") (pinfunction "2_2") (pintype "passive"))
      (node (ref "R36") (pin "1") (pinfunction "1_1") (pintype "passive"))
    )
    (net (code "121") (name "Net-(R20-Pad1)") (class "Default")
      (node (ref "R20") (pin "1") (pinfunction "1_1") (pintype "passive"))
      (node (ref "R36") (pin "2") (pinfunction "2_2") (pintype "passive"))
      (node (ref "R37") (pin "1") (pinfunction "1_1") (pintype "passive"))
    )
    (net (code "122") (name "Net-(R22-Pad2)") (class "Default")
      (node (ref "R22") (pin "2") (pinfunction "2_2") (pintype "passive"))
      (node (ref "R23") (pin "1") (pinfunction "1_1") (pintype "passive"))
      (node (ref "R6") (pin "1") (pinfunction "1_1") (pintype "passive"))
    )
    (net (code "123") (name "Net-(R23-Pad2)") (class "Default")
      (node (ref "R23") (pin "2") (pinfunction "2_2") (pintype "passive"))
      (node (ref "R24") (pin "1") (pinfunction "1_1") (pintype "passive"))
      (node (ref "R7") (pin "1") (pinfunction "1_1") (pintype "passive"))
    )
    (net (code "124") (name "Net-(R24-Pad2)") (class "Default")
      (node (ref "R24") (pin "2") (pinfunction "2_2") (pintype "passive"))
      (node (ref "R25") (pin "1") (pinfunction "1_1") (pintype "passive"))
      (node (ref "R8") (pin "1") (pinfunction "1_1") (pintype "passive"))
    )
    (net (code "125") (name "Net-(R25-Pad2)") (class "Default")
      (node (ref "R25") (pin "2") (pinfunction "2_2") (pintype "passive"))
      (node (ref "R26") (pin "1") (pinfunction "1_1") (pintype "passive"))
      (node (ref "R9") (pin "1") (pinfunction "1_1") (pintype "passive"))
    )
    (net (code "126") (name "Q") (class "Default")
      (node (ref "IC3") (pin "23") (pinfunction "23FB3MC2-I/O/GCK2_23") (pintype "bidirectional"))
      (node (ref "X1") (pin "7") (pinfunction "Q_7") (pintype "passive"))
    )
    (net (code "127") (name "R{slash}~{W}") (class "Default")
      (node (ref "IC3") (pin "36") (pinfunction "36FB5MC5_36") (pintype "bidirectional"))
      (node (ref "X1") (pin "18") (pinfunction "R/~{W}_18") (pintype "passive"))
    )
    (net (code "128") (name "SCK") (class "Default")
      (node (ref "IC1") (pin "6") (pinfunction "C_6") (pintype "input"))
      (node (ref "IC3") (pin "65") (pinfunction "65FB8MC6_65") (pintype "bidirectional"))
    )
    (net (code "129") (name "SND") (class "Default")
      (node (ref "C17") (pin "-") (pinfunction "-_-") (pintype "passive"))
      (node (ref "X1") (pin "35") (pinfunction "SND_35") (pintype "passive"))
    )
    (net (code "130") (name "SS") (class "Default")
      (node (ref "IC1") (pin "1") (pinfunction "~{S}_1") (pintype "input"))
      (node (ref "IC3") (pin "67") (pinfunction "67FB8MC9_67") (pintype "bidirectional"))
    )
    (net (code "131") (name "SS2") (class "Default")
      (node (ref "IC3") (pin "68") (pinfunction "68FB8MC11_68") (pintype "bidirectional"))
    )
    (net (code "132") (name "SW0") (class "Default")
      (node (ref "IC3") (pin "74") (pinfunction "74FB6MC2_74") (pintype "bidirectional"))
      (node (ref "R3") (pin "1") (pinfunction "1_1") (pintype "passive"))
      (node (ref "S1") (pin "1") (pinfunction "P_1") (pintype "passive"))
    )
    (net (code "133") (name "SW1") (class "Default")
      (node (ref "IC3") (pin "79") (pinfunction "79FB6MC9_79") (pintype "bidirectional"))
      (node (ref "R4") (pin "1") (pinfunction "1_1") (pintype "passive"))
      (node (ref "S2") (pin "2") (pinfunction "S_2") (pintype "passive"))
    )
    (net (code "134") (name "unconnected-(IC2A-D8-Pad30)") (class "Default")
      (node (ref "IC2") (pin "30") (pinfunction "D8_30") (pintype "tri_state"))
    )
    (net (code "135") (name "unconnected-(IC2A-D9-Pad32)") (class "Default")
      (node (ref "IC2") (pin "32") (pinfunction "D9_32") (pintype "tri_state"))
    )
    (net (code "136") (name "unconnected-(IC2A-D10-Pad34)") (class "Default")
      (node (ref "IC2") (pin "34") (pinfunction "D10_34") (pintype "tri_state"))
    )
    (net (code "137") (name "unconnected-(IC2A-D11-Pad36)") (class "Default")
      (node (ref "IC2") (pin "36") (pinfunction "D11_36") (pintype "tri_state"))
    )
    (net (code "138") (name "unconnected-(IC2A-D12-Pad39)") (class "Default")
      (node (ref "IC2") (pin "39") (pinfunction "D12_39") (pintype "tri_state"))
    )
    (net (code "139") (name "unconnected-(IC2A-D13-Pad41)") (class "Default")
      (node (ref "IC2") (pin "41") (pinfunction "D13_41") (pintype "tri_state"))
    )
    (net (code "140") (name "unconnected-(IC2A-D14-Pad43)") (class "Default")
      (node (ref "IC2") (pin "43") (pinfunction "D14_43") (pintype "tri_state"))
    )
    (net (code "141") (name "unconnected-(X1B-~{HALT}-Pad3)") (class "Default")
      (node (ref "X1") (pin "3") (pinfunction "~{HALT}_3") (pintype "passive"))
    )
    (net (code "142") (name "unconnected-(X1B-~{NMI}-Pad4)") (class "Default")
      (node (ref "X1") (pin "4") (pinfunction "~{NMI}_4") (pintype "passive"))
    )
    (net (code "143") (name "unconnected-(X2-Pad4)") (class "Default")
      (node (ref "X2") (pin "4") (pinfunction "4_4") (pintype "passive"))
    )
    (net (code "144") (name "unconnected-(X2-Pad5)") (class "Default")
      (node (ref "X2") (pin "5") (pinfunction "5_5") (pintype "passive"))
    )
    (net (code "145") (name "~{BRESET}") (class "Default")
      (node (ref "IC2") (pin "12") (pinfunction "~{RESET}_12") (pintype "input"))
      (node (ref "IC3") (pin "9") (pinfunction "9FB2MC15_9") (pintype "bidirectional"))
    )
    (net (code "146") (name "~{CART}") (class "Default")
      (node (ref "IC3") (pin "25") (pinfunction "25FB3MC6_25") (pintype "bidirectional"))
      (node (ref "X1") (pin "8") (pinfunction "~{CART}_8") (pintype "passive"))
    )
    (net (code "147") (name "~{CTS}") (class "Default")
      (node (ref "IC3") (pin "55") (pinfunction "55FB7MC9_55") (pintype "bidirectional"))
      (node (ref "X1") (pin "32") (pinfunction "~{CTS}_32") (pintype "passive"))
    )
    (net (code "148") (name "~{OE}") (class "Default")
      (node (ref "IC2") (pin "28") (pinfunction "~{OE}_28") (pintype "input"))
      (node (ref "IC3") (pin "81") (pinfunction "81FB6MC12_81") (pintype "bidirectional"))
    )
    (net (code "149") (name "~{RB}") (class "Default")
      (node (ref "IC2") (pin "15") (pinfunction "~{RB}_15") (pintype "output"))
    )
    (net (code "150") (name "~{RESET}") (class "Default")
      (node (ref "IC3") (pin "99") (pinfunction "99FB2MC2-I/O/GSR_99") (pintype "bidirectional"))
      (node (ref "R2") (pin "1") (pinfunction "1_1") (pintype "passive"))
      (node (ref "R48") (pin "1") (pinfunction "1_1") (pintype "passive"))
      (node (ref "X1") (pin "5") (pinfunction "~{RESET}_5") (pintype "passive"))
    )
    (net (code "151") (name "~{SCS}") (class "Default")
      (node (ref "IC3") (pin "58") (pinfunction "58FB7MC12_58") (pintype "bidirectional"))
      (node (ref "X1") (pin "36") (pinfunction "~{SCS}_36") (pintype "passive"))
    )
    (net (code "152") (name "~{SLENB}") (class "Default")
      (node (ref "IC3") (pin "61") (pinfunction "61FB7MC17_61") (pintype "bidirectional"))
      (node (ref "X1") (pin "40") (pinfunction "~{SLENB}_40") (pintype "passive"))
    )
    (net (code "153") (name "~{WE}") (class "Default")
      (node (ref "IC2") (pin "11") (pinfunction "~{WE}_11") (pintype "input"))
      (node (ref "IC3") (pin "10") (pinfunction "10FB2MC17_10") (pintype "bidirectional"))
    )
  )
)
